# Shutdown_2019_v1_0.net
KiCad netlist of a schematic drawn in EAGLE
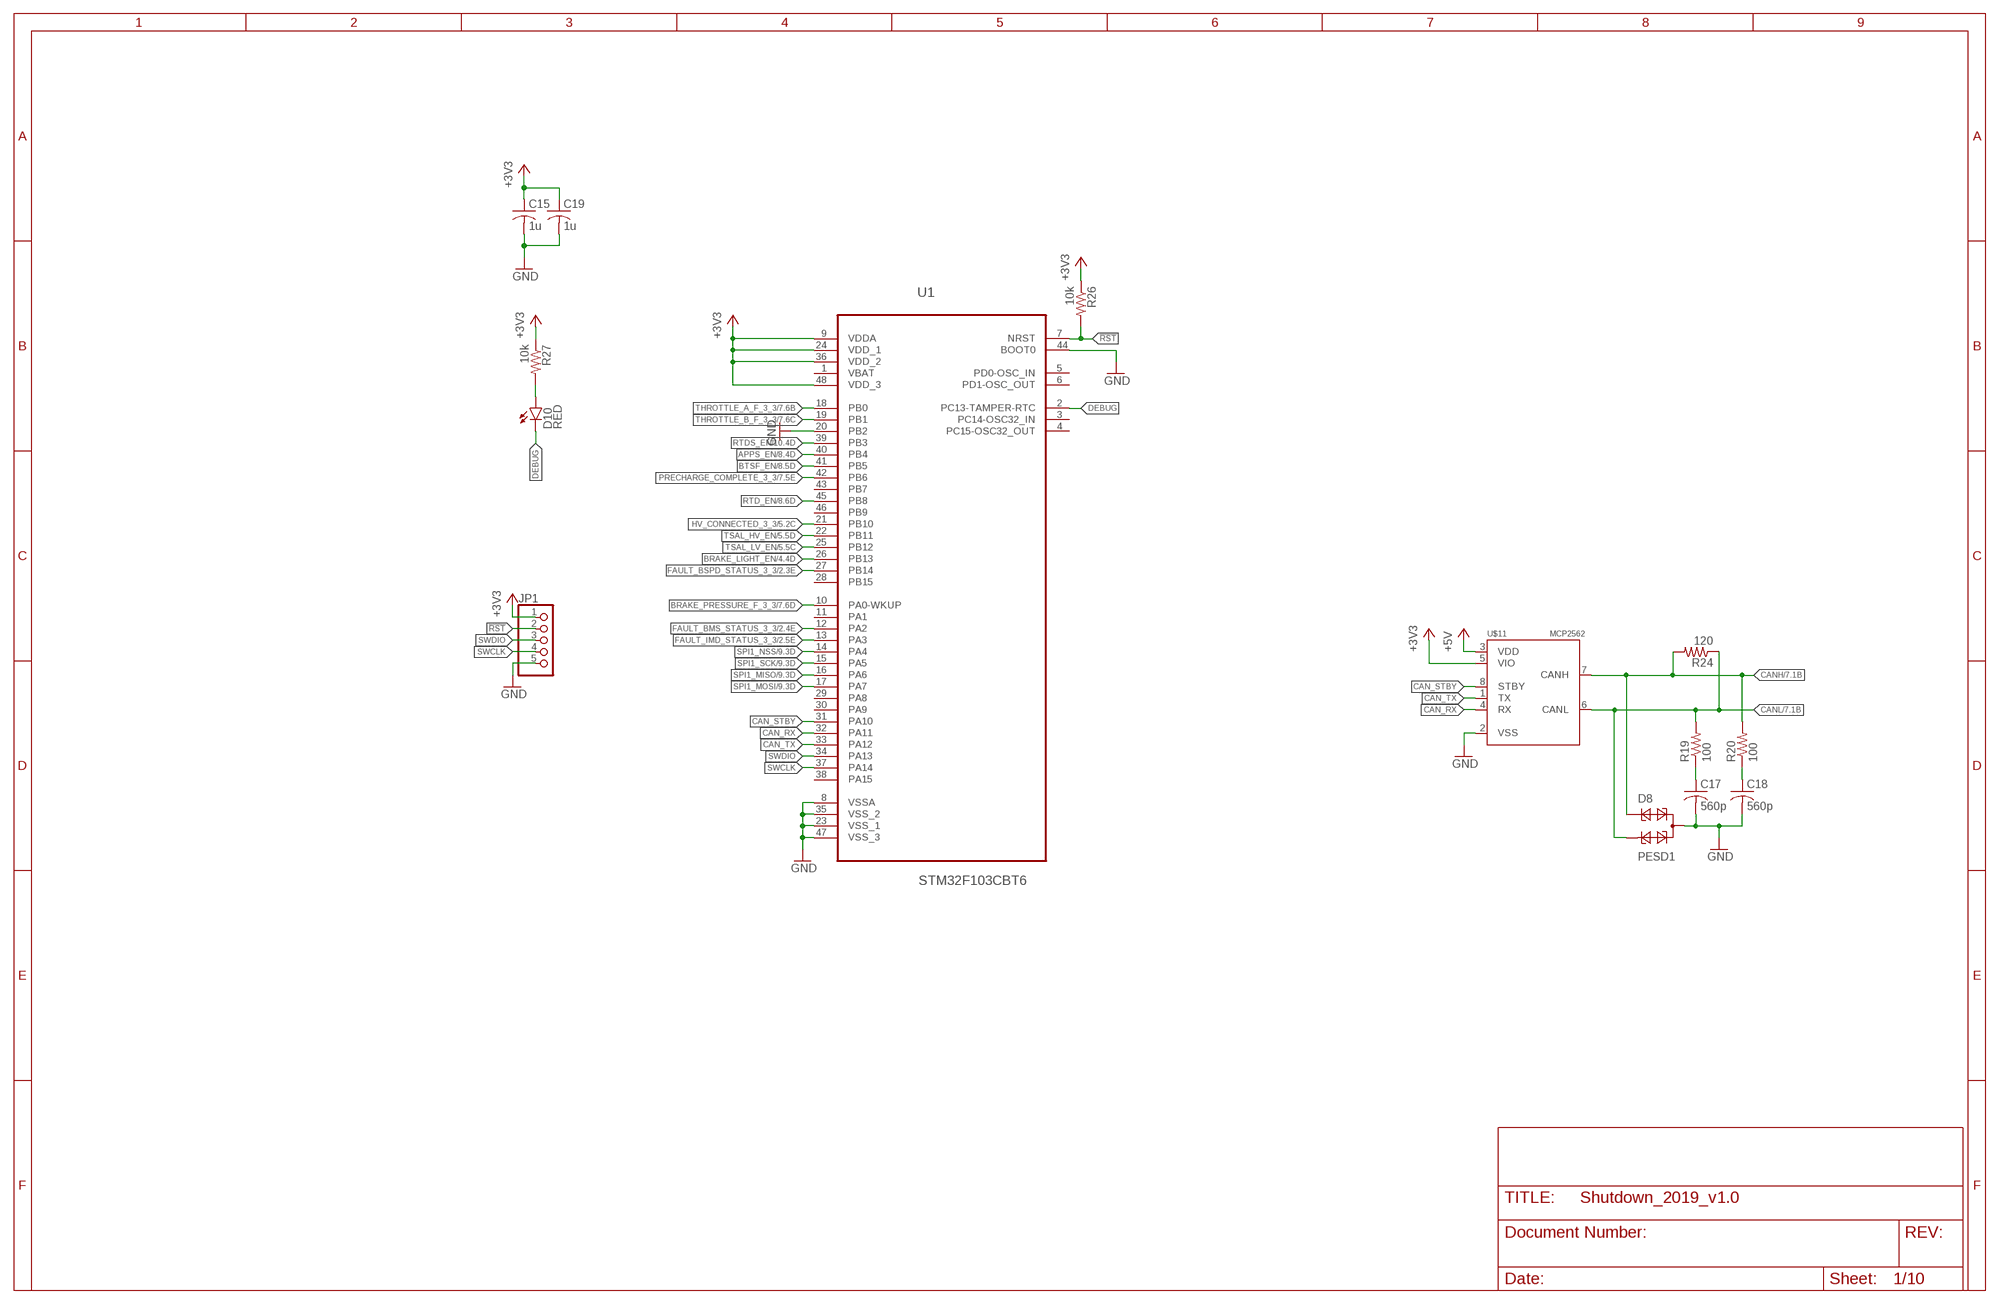
[diagram p0: schematic, sheet 1]
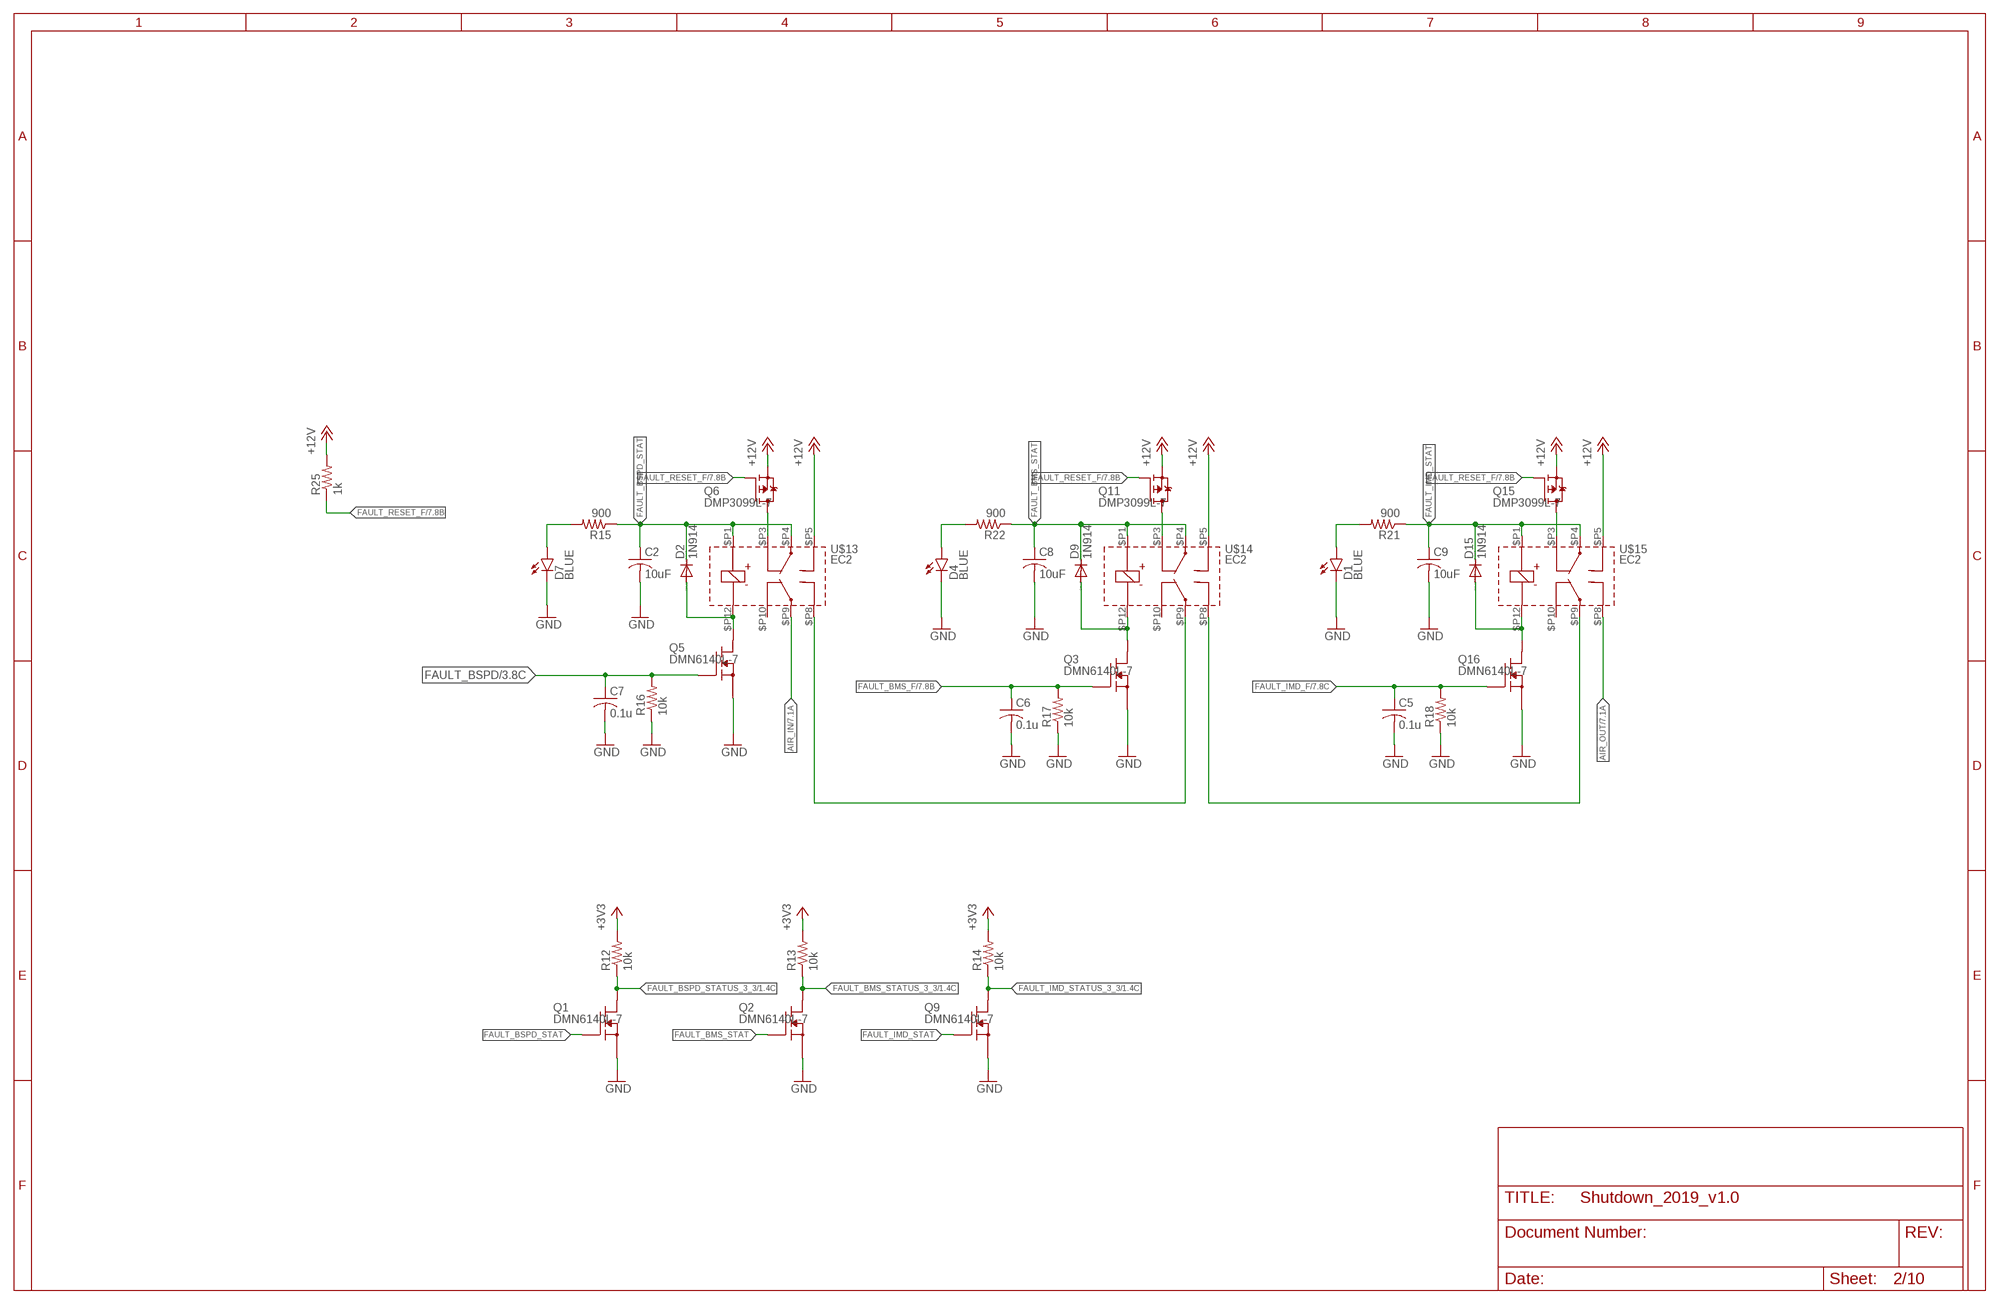
[diagram p1: schematic, sheet 2]
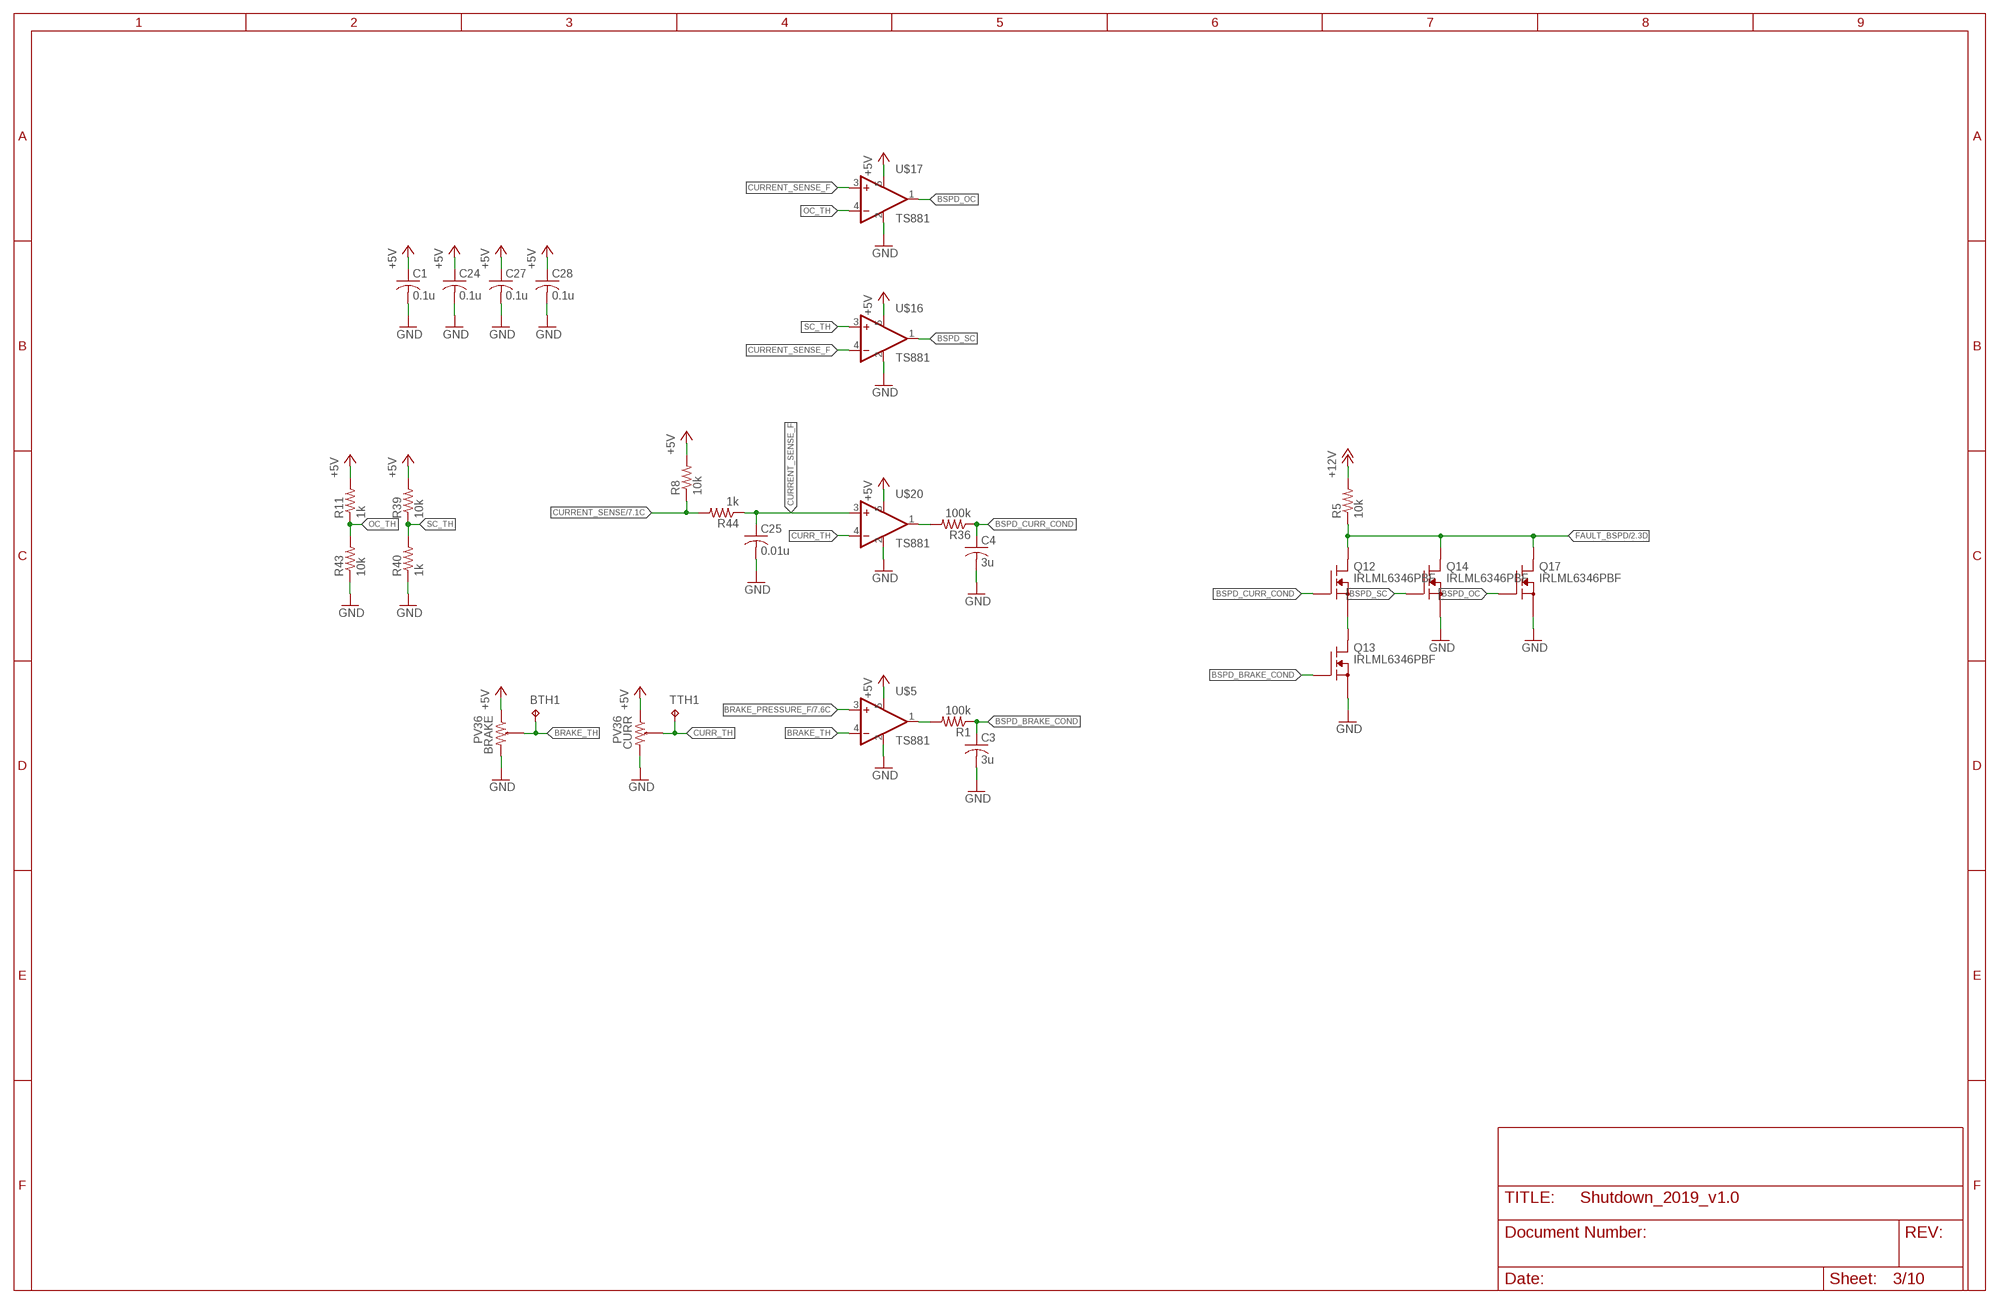
[diagram p2: schematic, sheet 3]
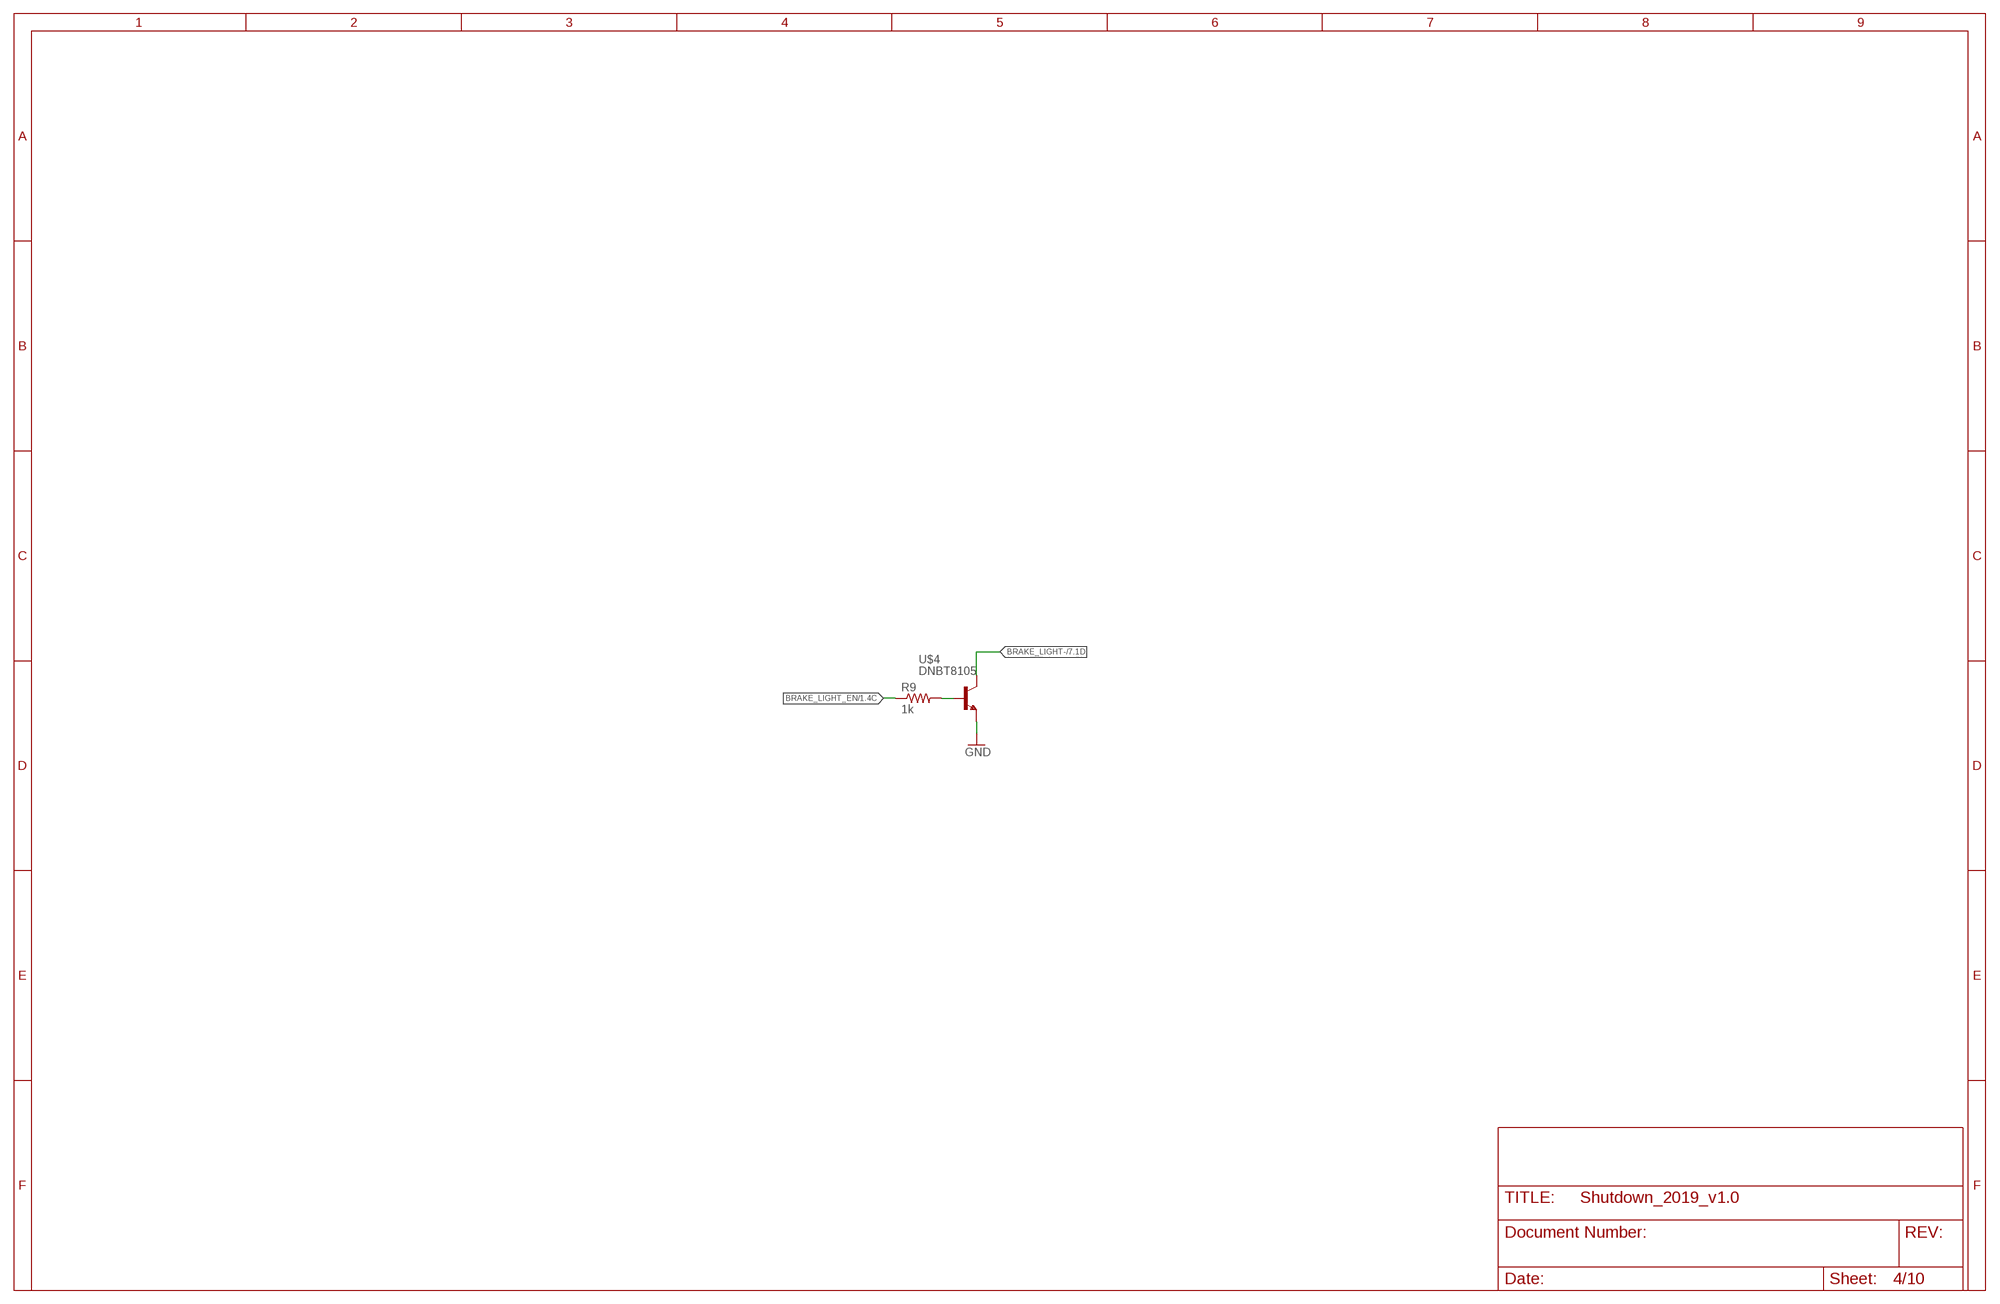
[diagram p3: schematic, sheet 4]
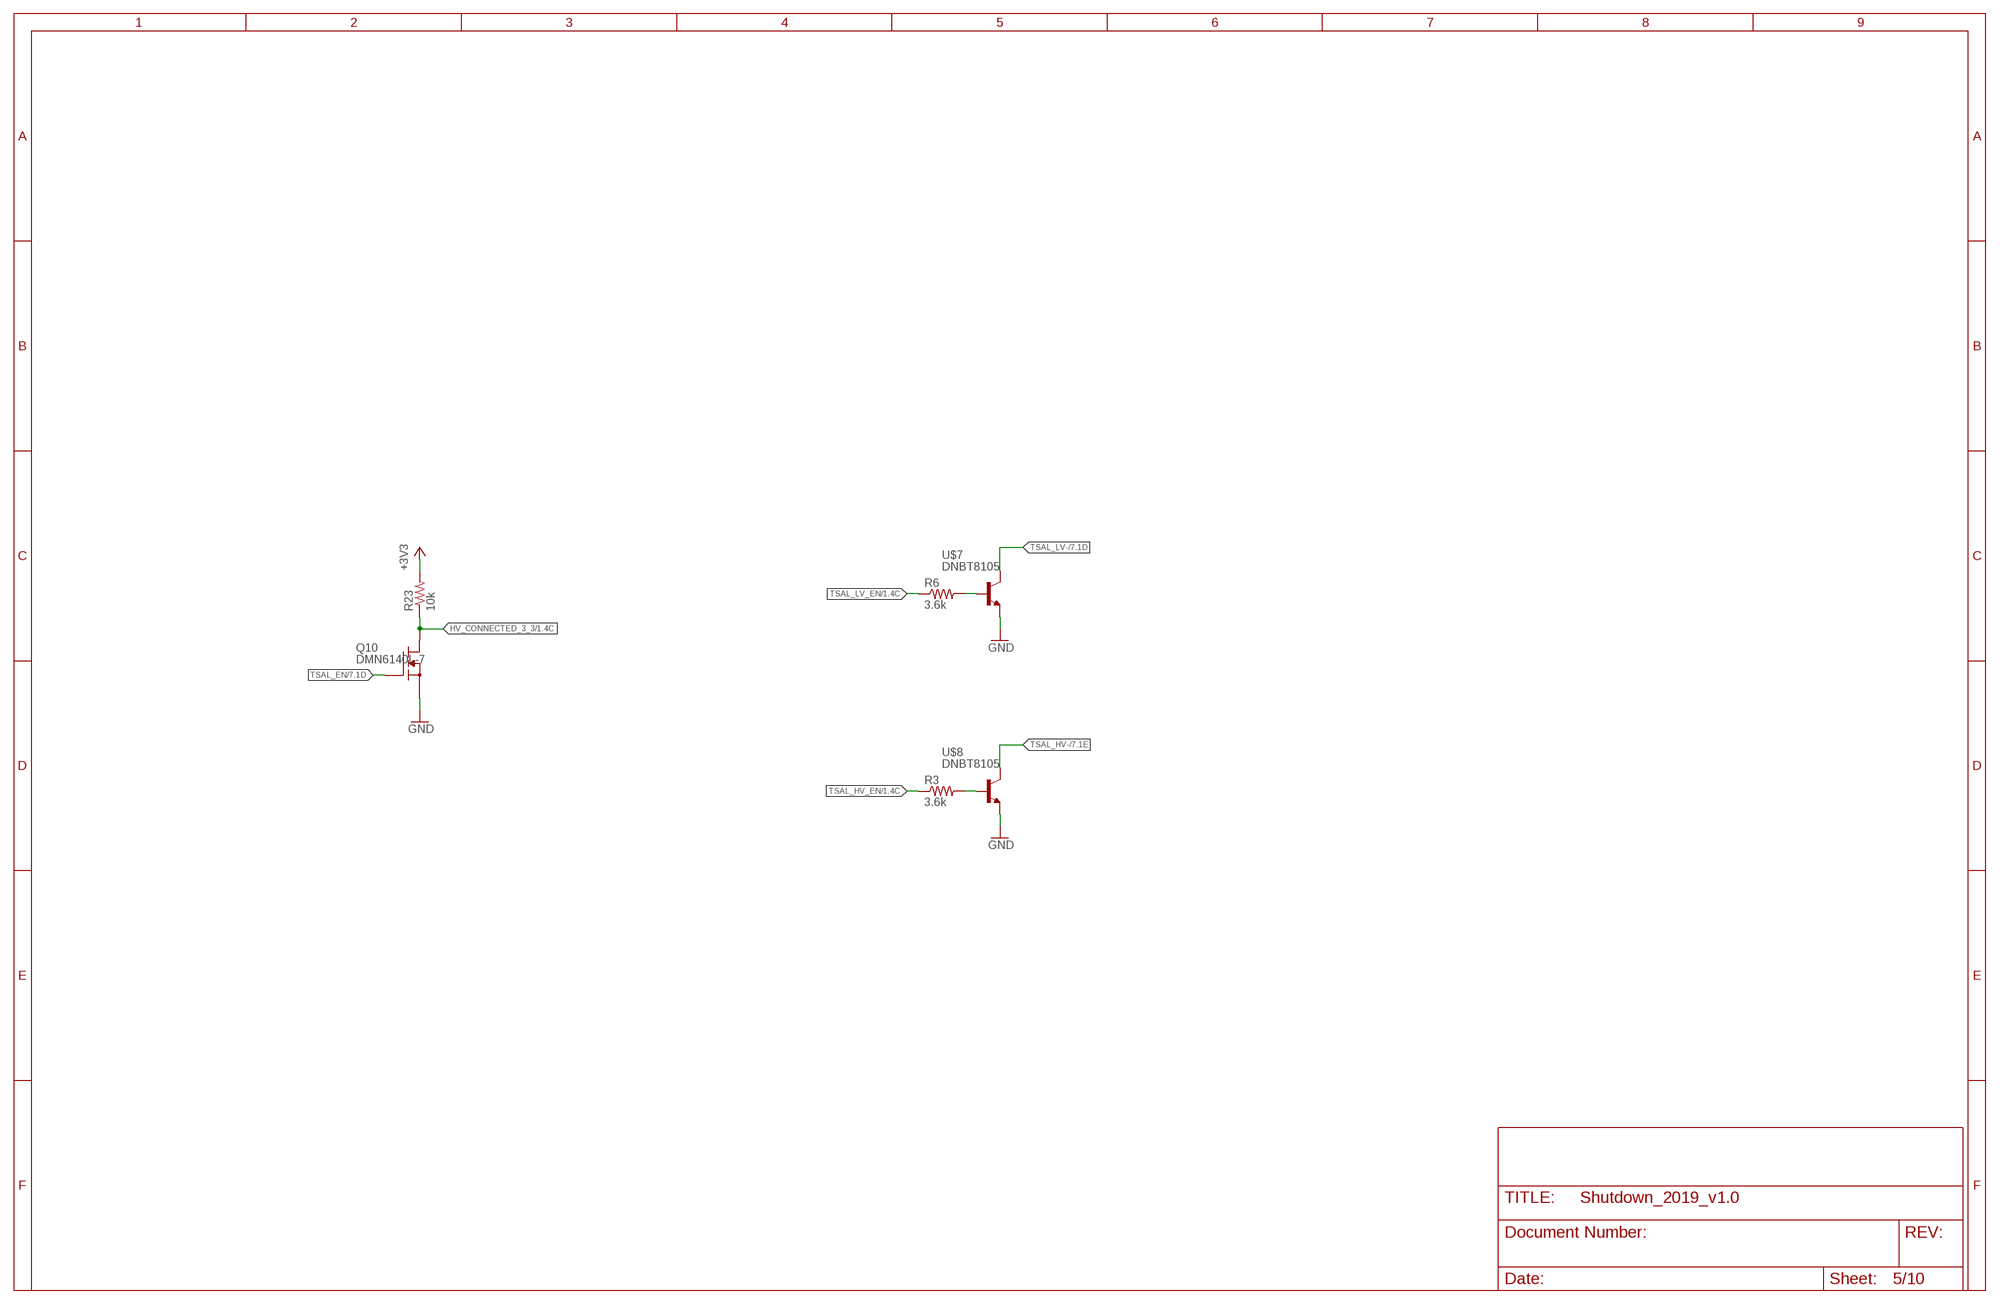
[diagram p4: schematic, sheet 5]
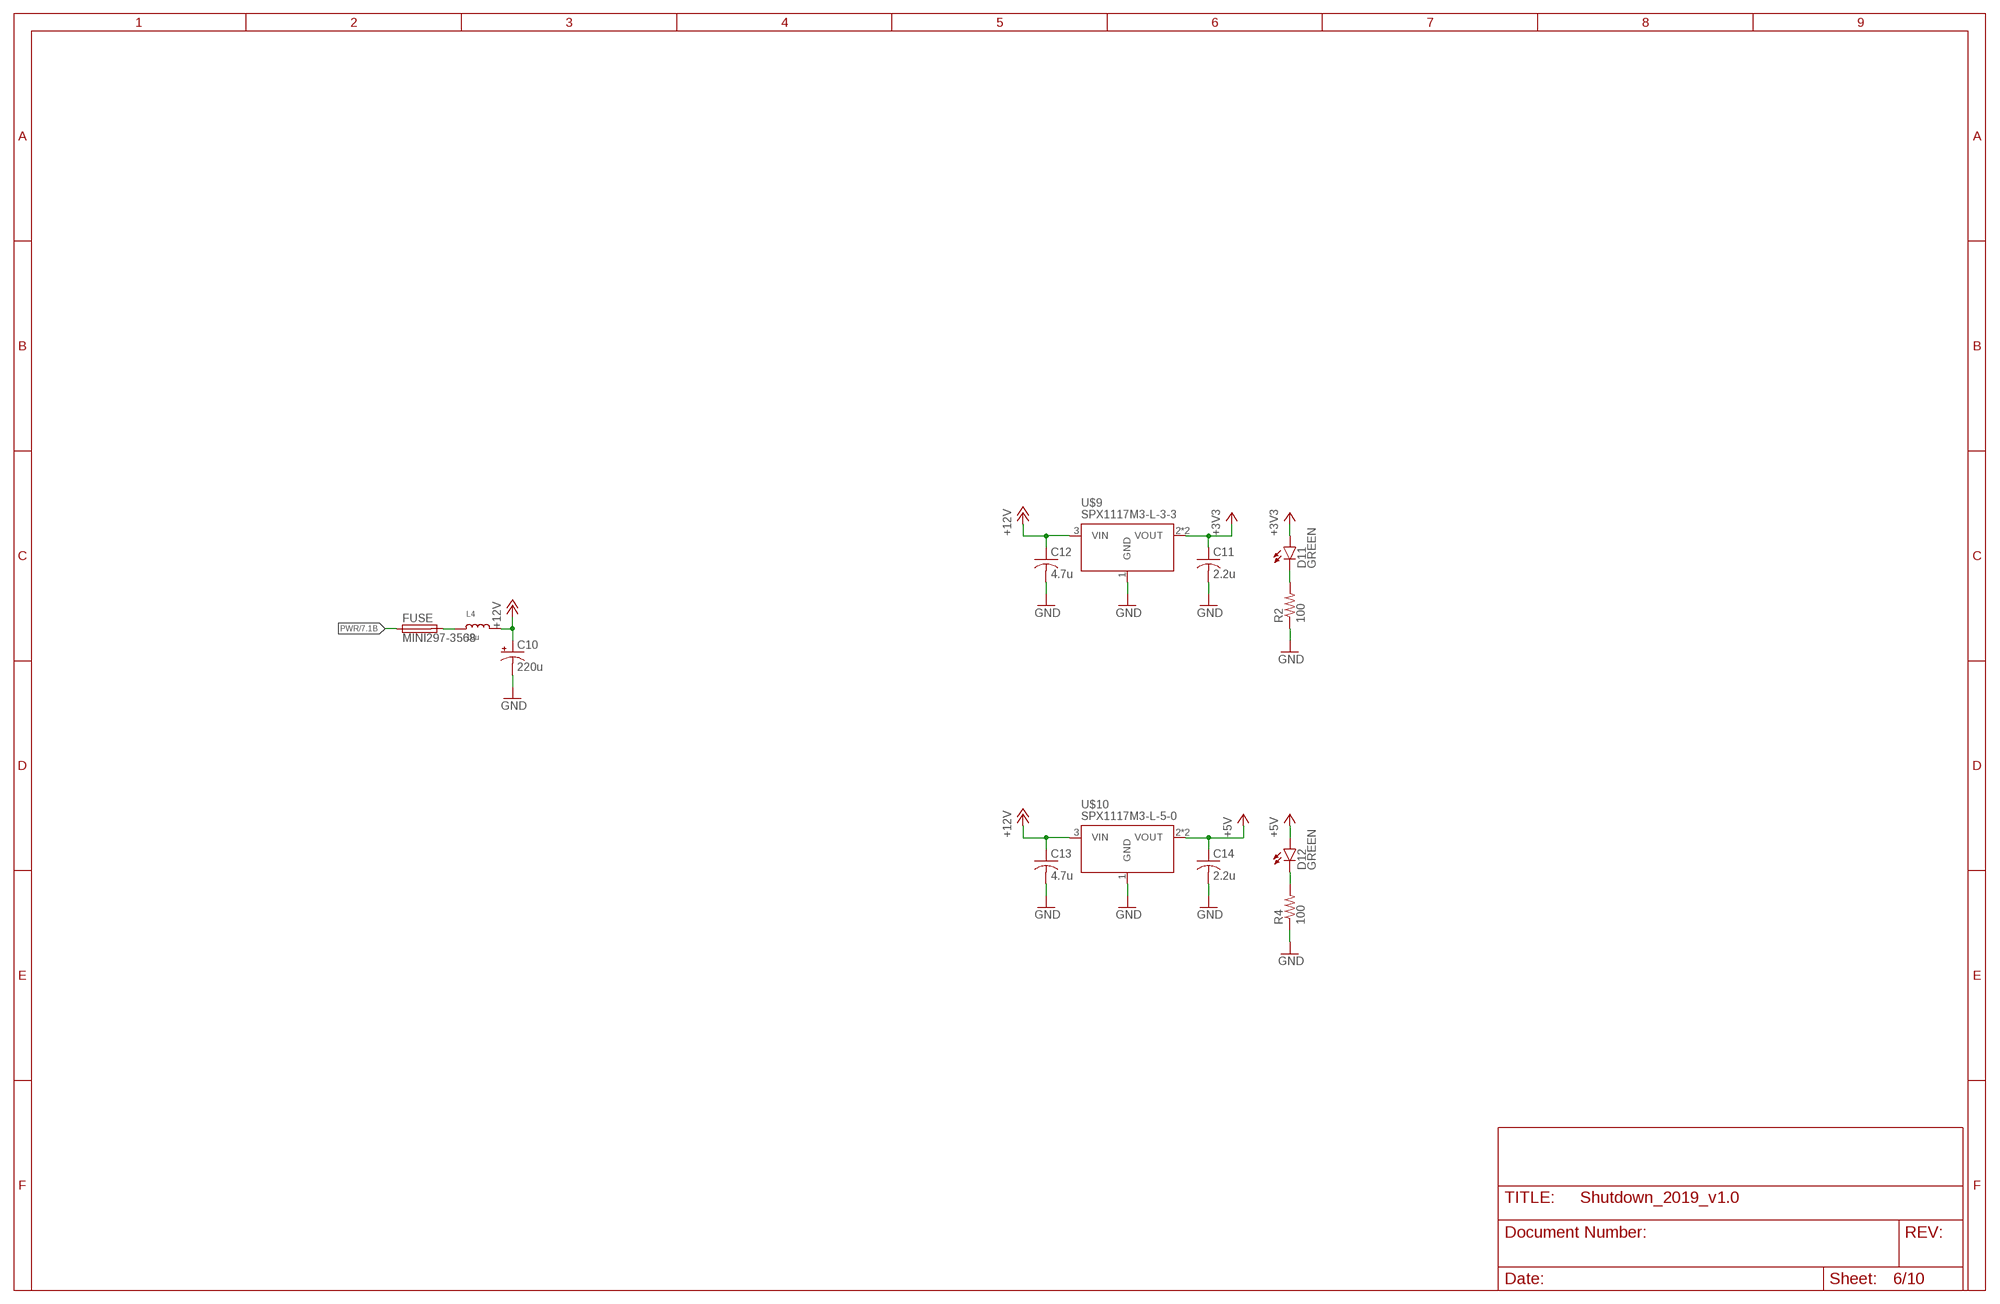
[diagram p5: schematic, sheet 6]
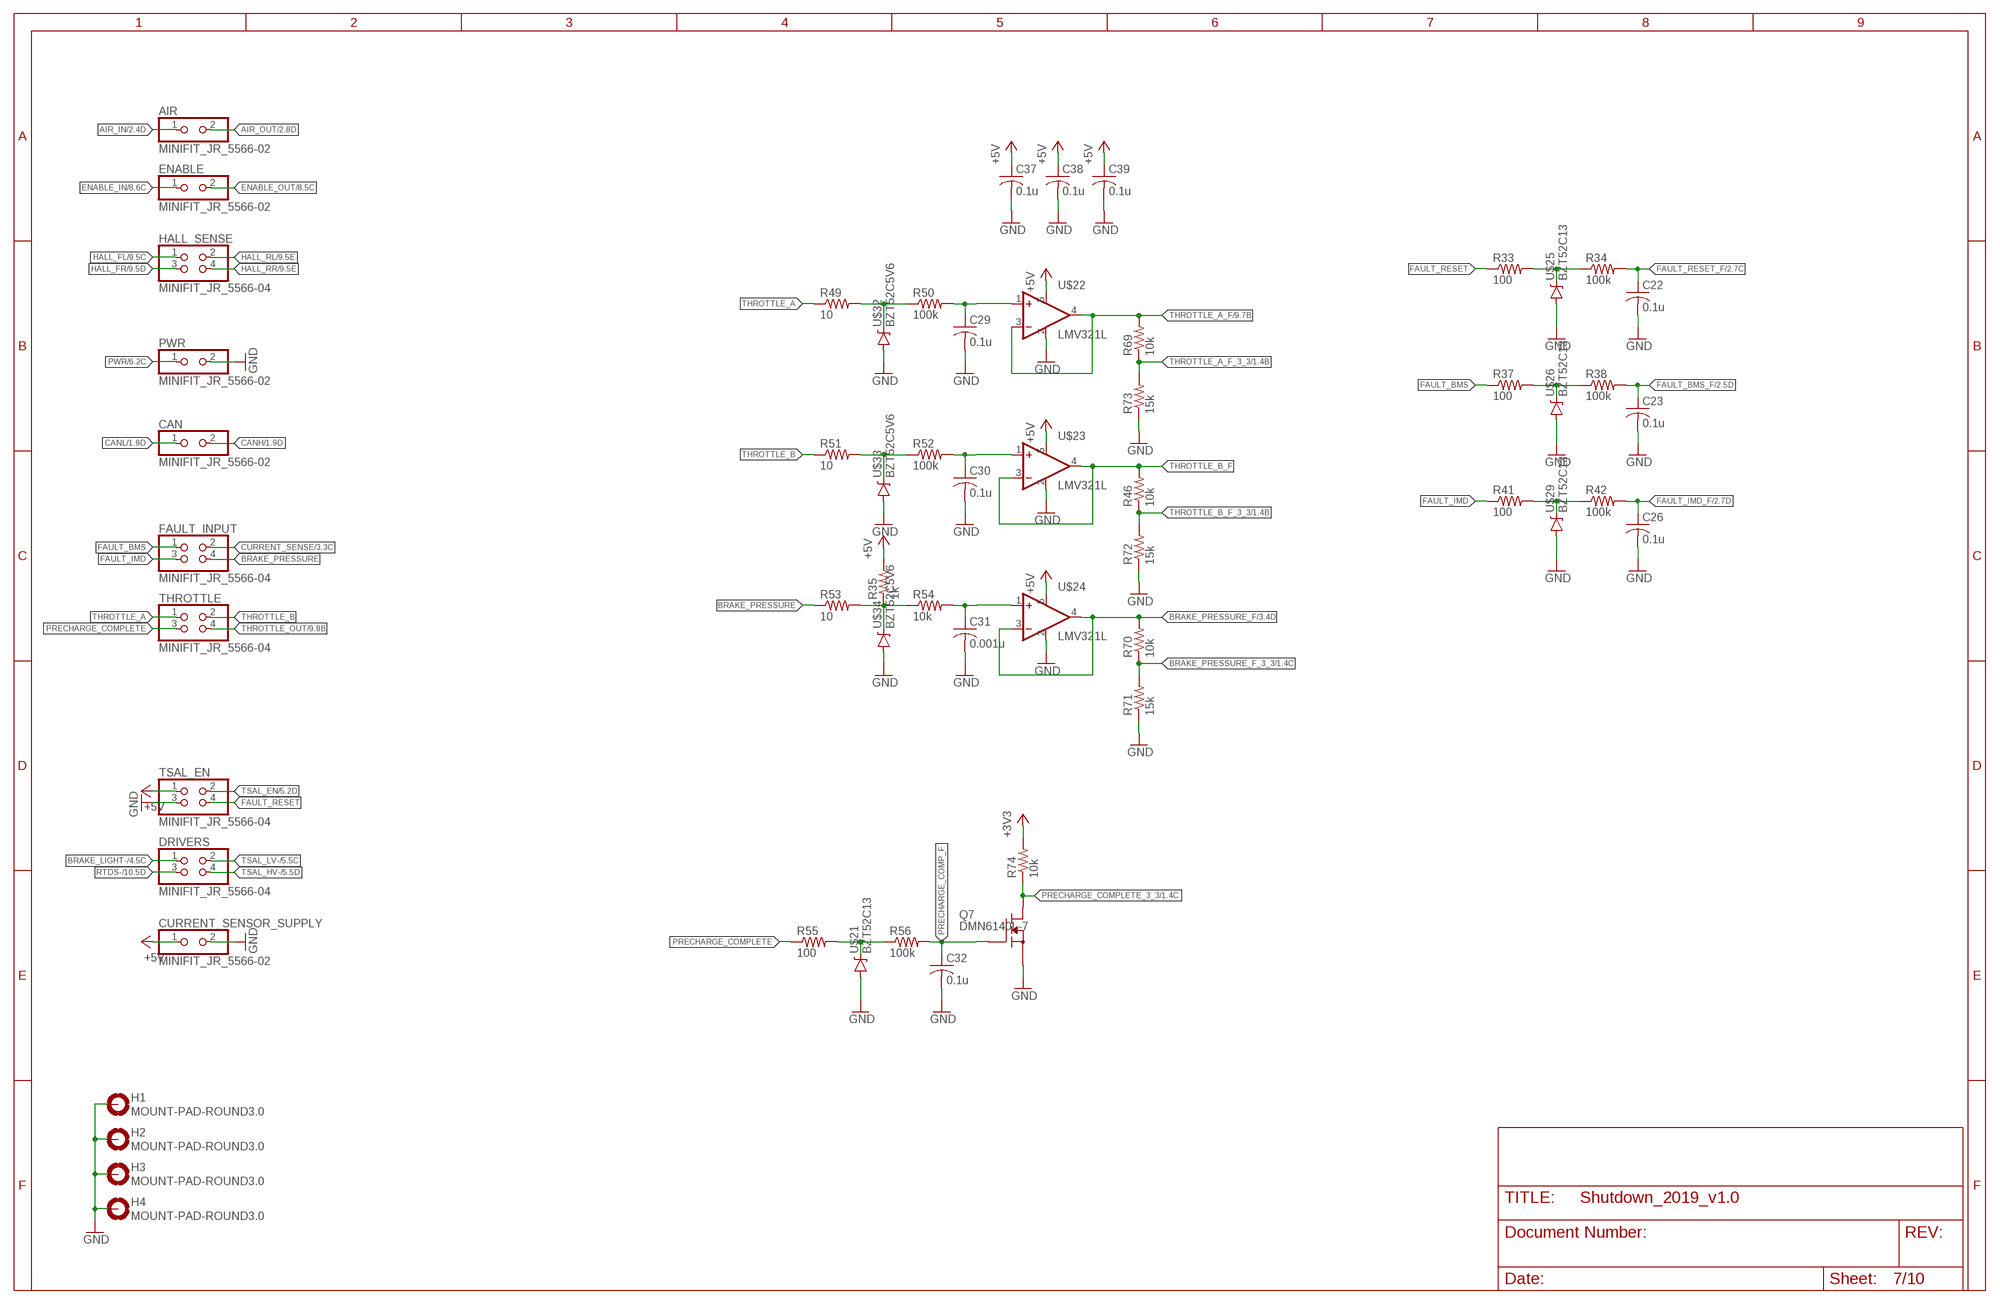
[diagram p6: schematic, sheet 7]
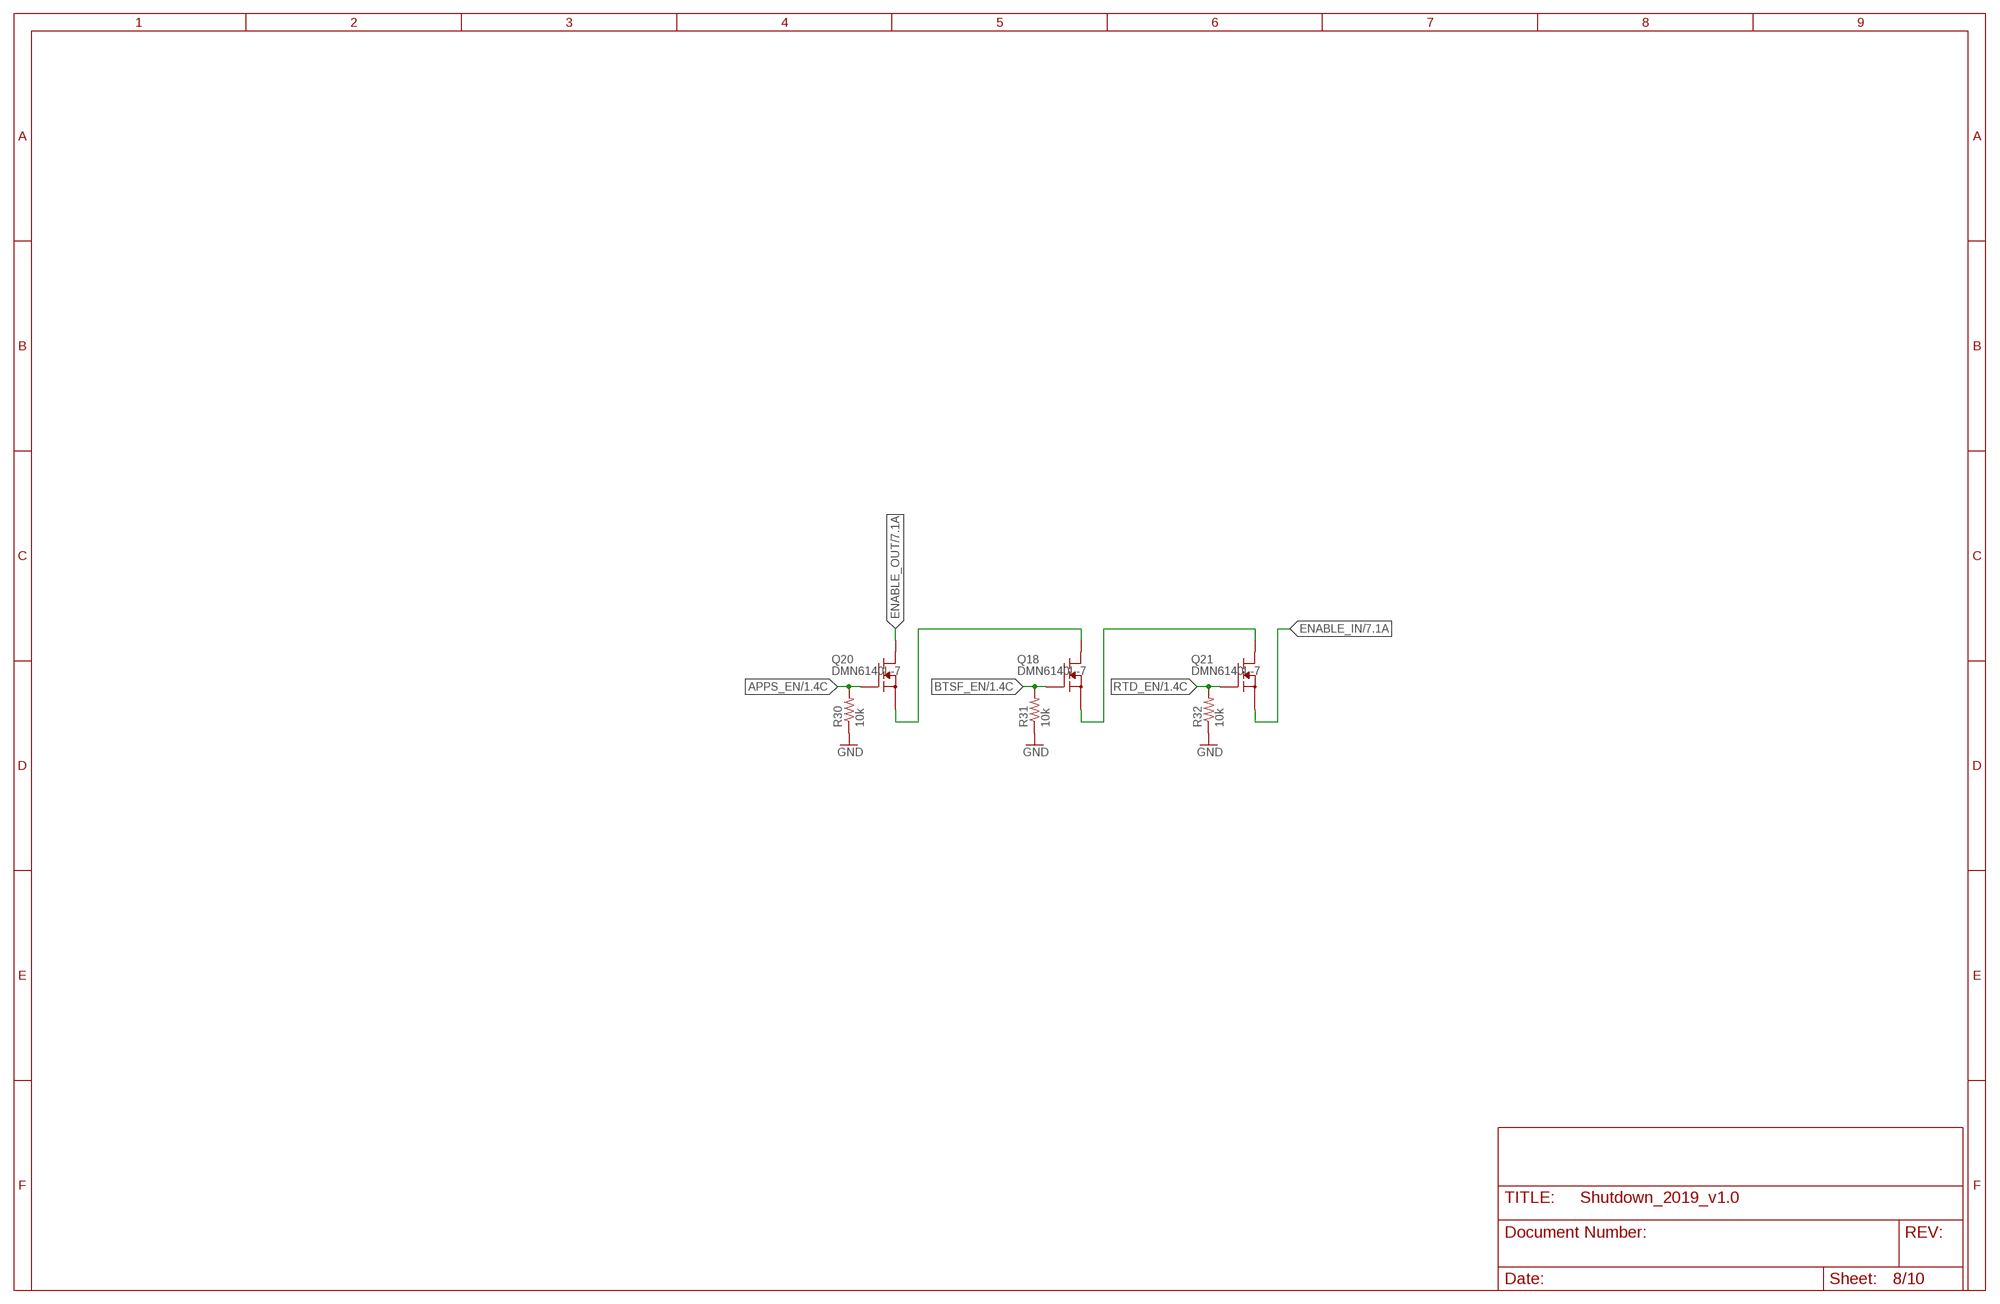
[diagram p7: schematic, sheet 8]
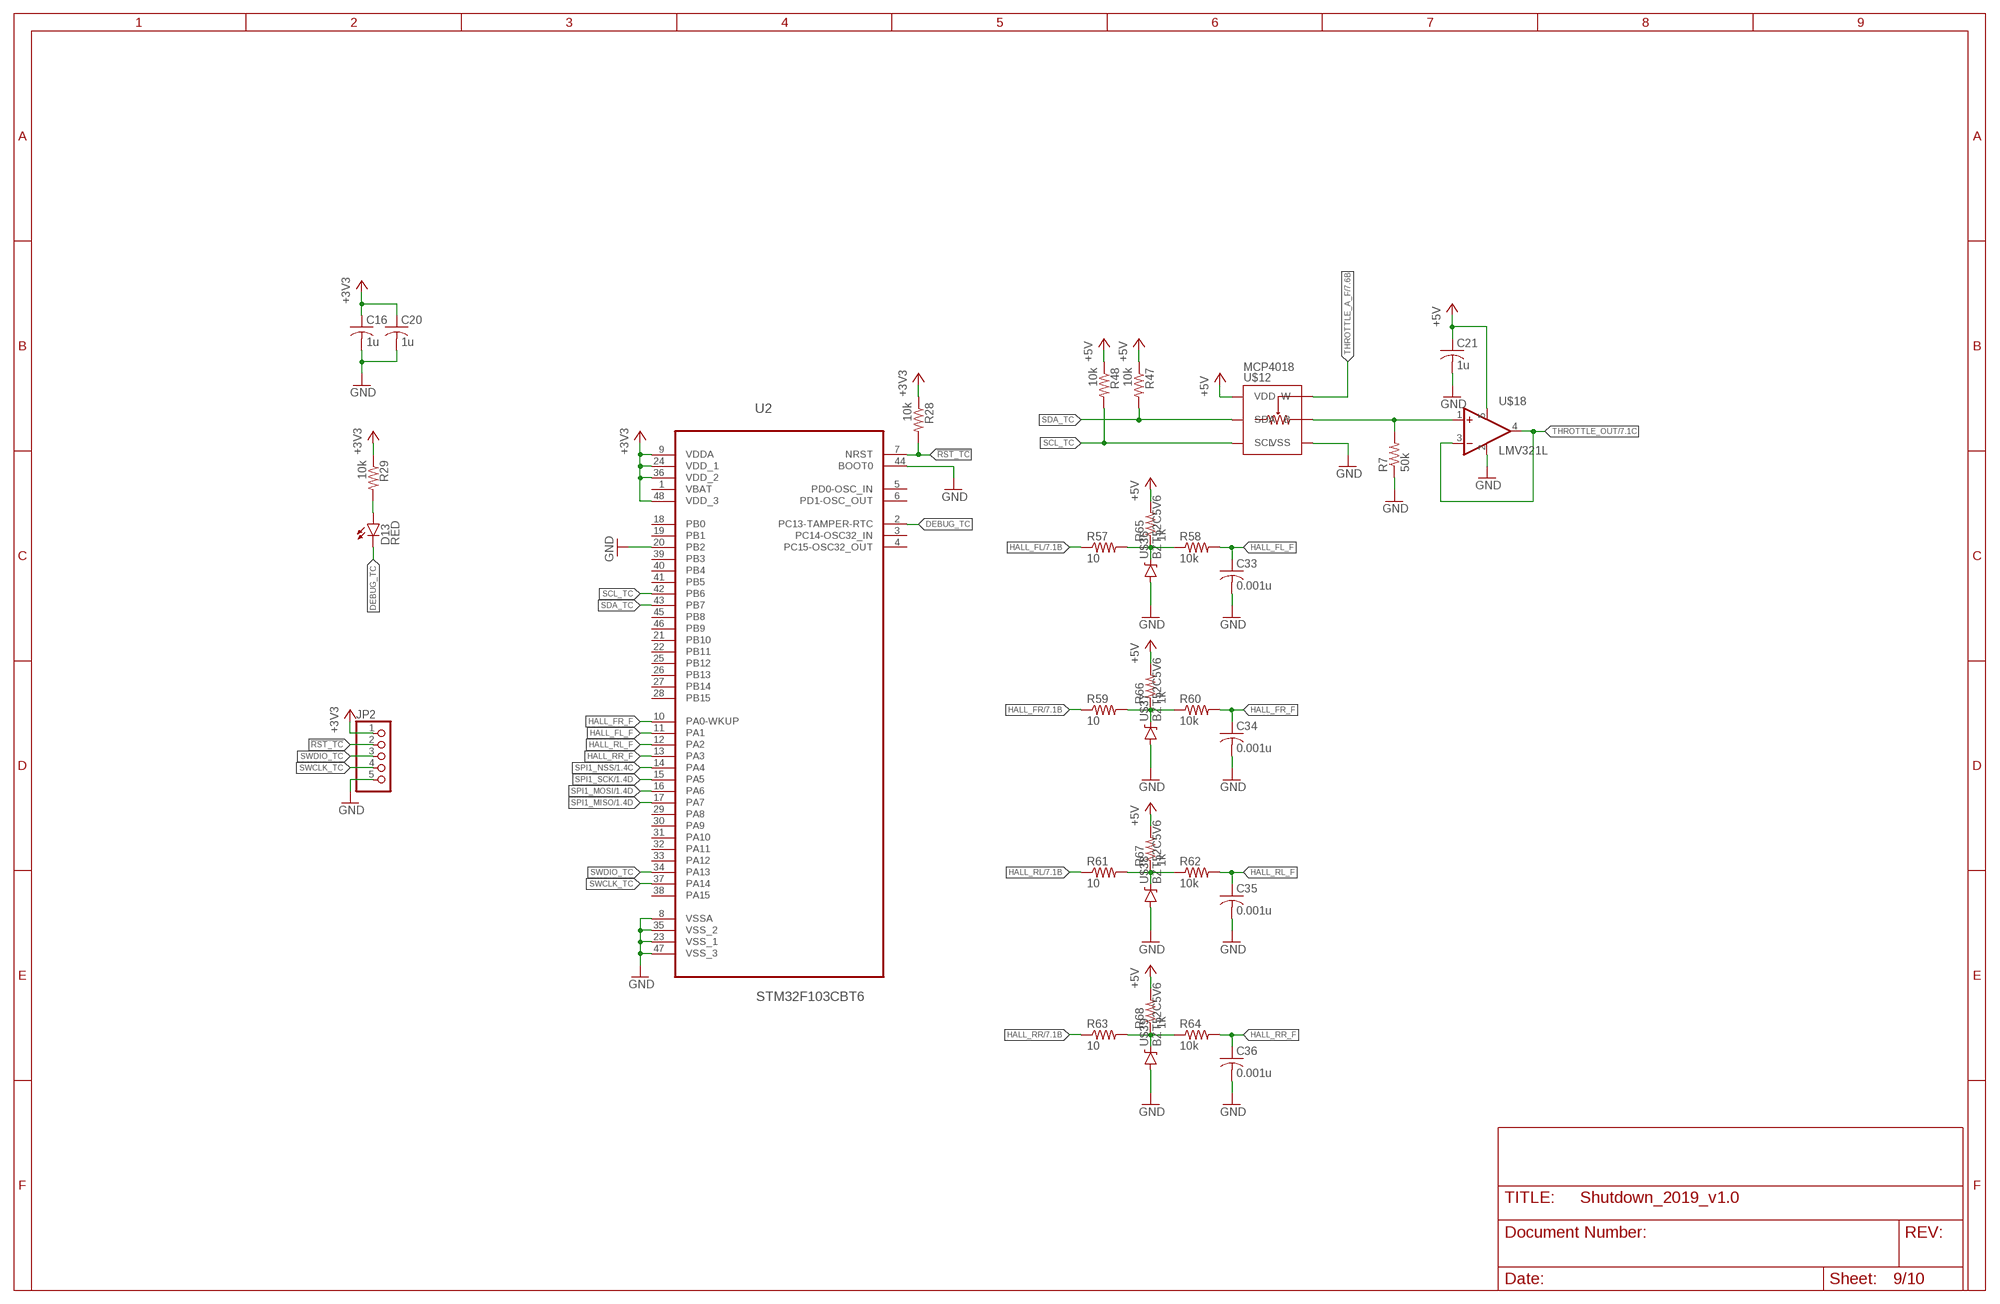
[diagram p8: schematic, sheet 9]
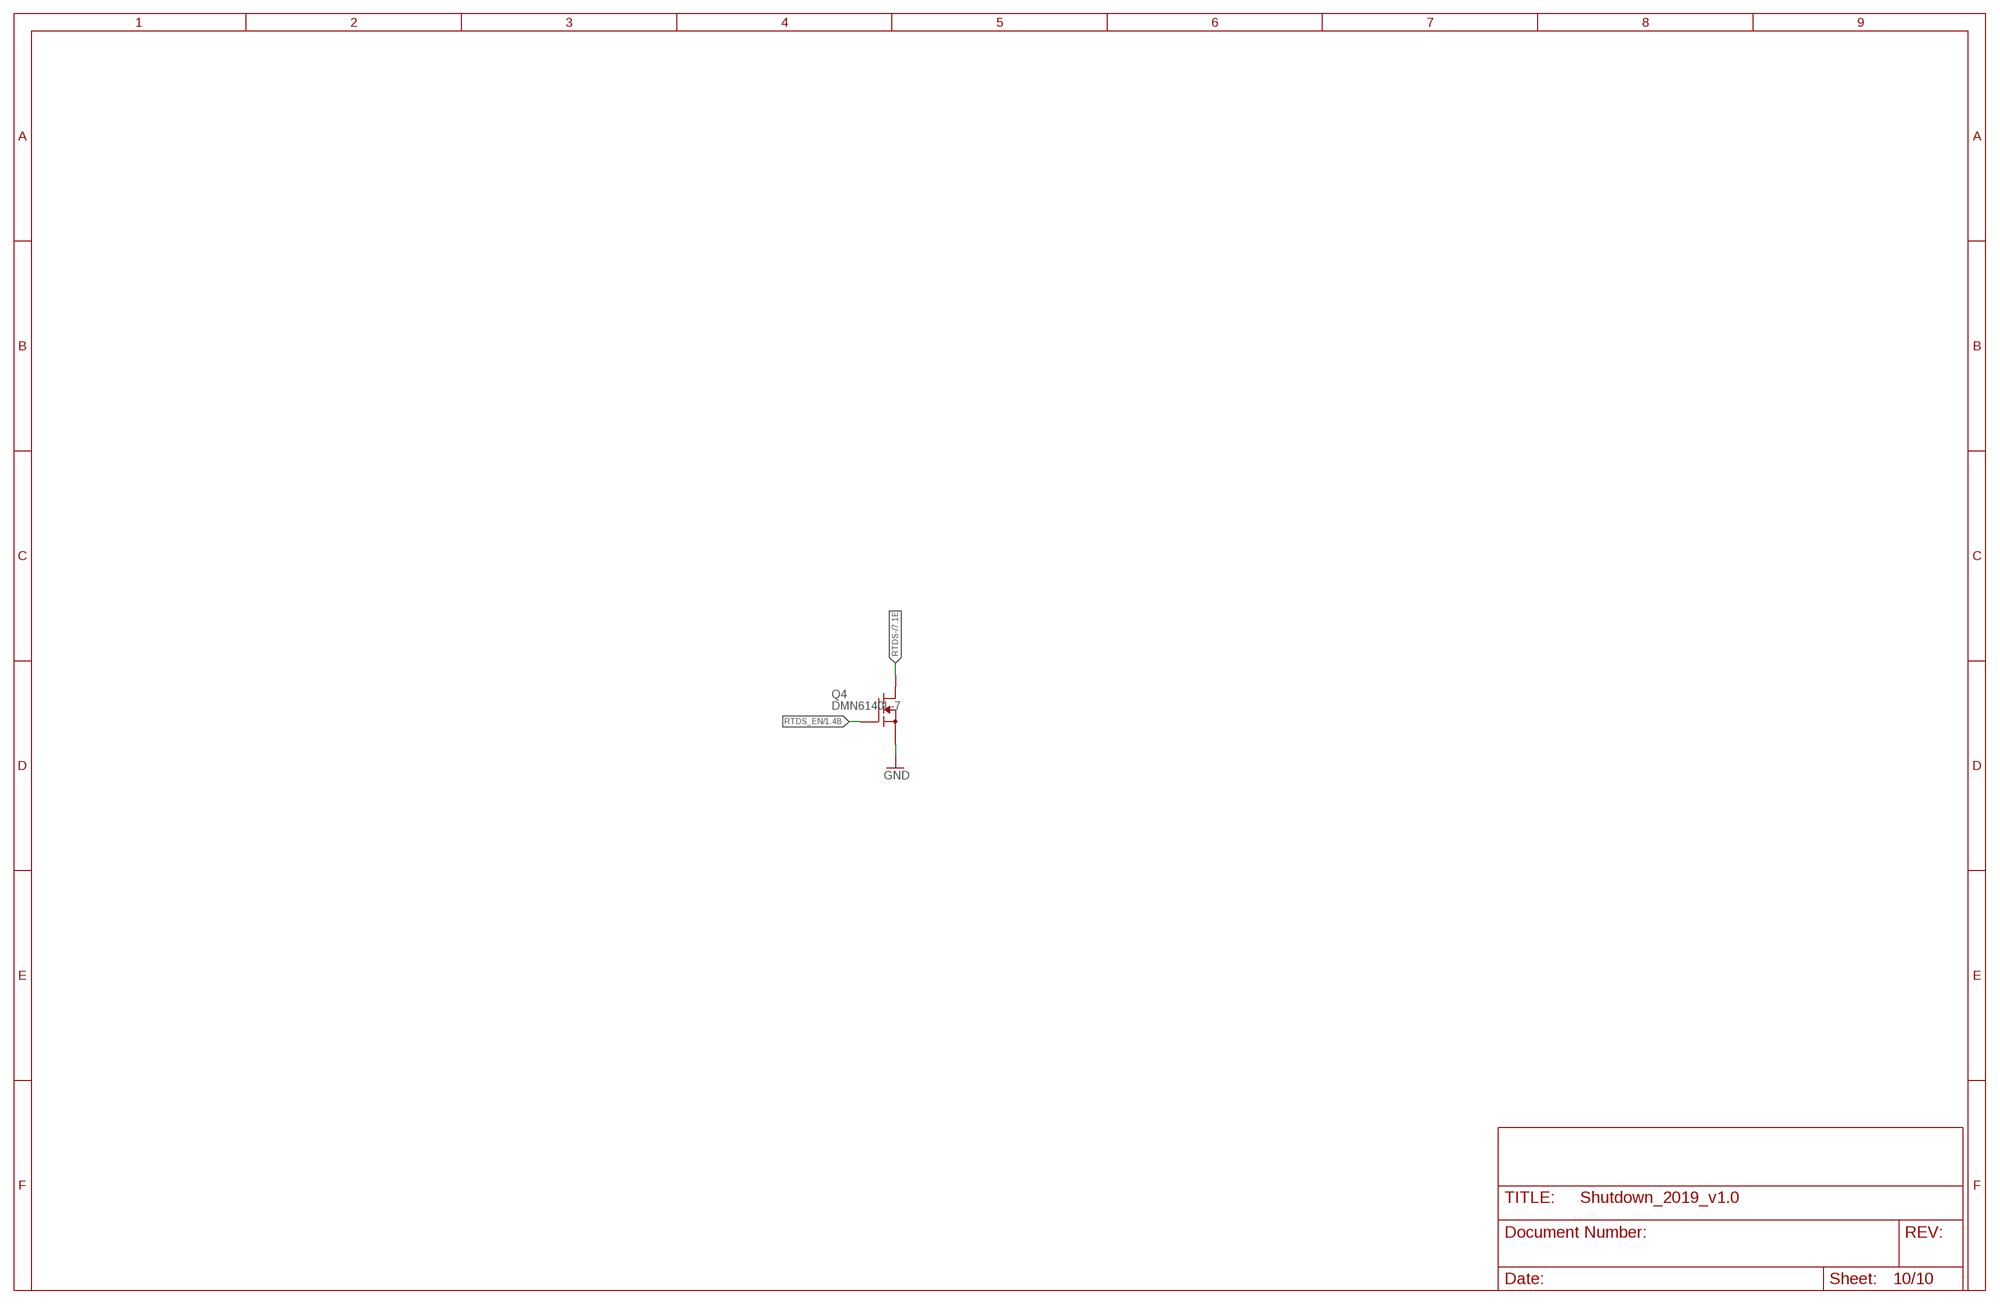
[diagram p9: schematic, sheet 10]

(export (version "E")
  (design (tool "Eeschema 10.0.6"))
  (components
    (comp (ref "C15")
      (value "1u")
      (footprint "eagle-import:C0805")
      (libsource (lib "eagle-import") (part "C-USC0805"))
    )
    (comp (ref "C17")
      (value "560p")
      (footprint "eagle-import:C0603")
      (libsource (lib "eagle-import") (part "C-USC0603"))
    )
    (comp (ref "C18")
      (value "560p")
      (footprint "eagle-import:C0603")
      (libsource (lib "eagle-import") (part "C-USC0603"))
    )
    (comp (ref "C19")
      (value "1u")
      (footprint "eagle-import:C0805")
      (libsource (lib "eagle-import") (part "C-USC0805"))
    )
    (comp (ref "D8")
      (value "PESD1")
      (footprint "eagle-import:SOT23")
      (libsource (lib "eagle-import") (part "PESD1CAN"))
    )
    (comp (ref "D10")
      (value "RED")
      (footprint "eagle-import:LED-0603")
      (libsource (lib "eagle-import") (part "LED-RED0603"))
    )
    (comp (ref "JP1")
      (value "PINHD-1X5")
      (footprint "eagle-import:1X05")
      (libsource (lib "eagle-import") (part "PINHD-1X5"))
    )
    (comp (ref "R19")
      (value "100")
      (footprint "eagle-import:R0603")
      (libsource (lib "eagle-import") (part "R-US_R0603"))
    )
    (comp (ref "R20")
      (value "100")
      (footprint "eagle-import:R0603")
      (libsource (lib "eagle-import") (part "R-US_R0603"))
    )
    (comp (ref "R24")
      (value "120")
      (footprint "eagle-import:R0603")
      (libsource (lib "eagle-import") (part "R-US_R0603"))
    )
    (comp (ref "R26")
      (value "10k")
      (footprint "eagle-import:R0603")
      (libsource (lib "eagle-import") (part "R-US_R0603"))
    )
    (comp (ref "R27")
      (value "10k")
      (footprint "eagle-import:R0603")
      (libsource (lib "eagle-import") (part "R-US_R0603"))
    )
    (comp (ref "U$11")
      (value "MCP2562")
      (footprint "eagle-import:SOIC8")
      (libsource (lib "eagle-import") (part "MCP2562"))
    )
    (comp (ref "U1")
      (value "STM32F103CBT6")
      (footprint "eagle-import:QFP50P900X900X160-48N")
      (libsource (lib "eagle-import") (part "STM32F103CBT6"))
    )
    (comp (ref "C10")
      (value "220u")
      (footprint "eagle-import:E2,5-7")
      (libsource (lib "eagle-import") (part "CPOL-USE2.5-7"))
    )
    (comp (ref "C11")
      (value "2.2u")
      (footprint "eagle-import:C0805")
      (libsource (lib "eagle-import") (part "C-USC0805"))
    )
    (comp (ref "C12")
      (value "4.7u")
      (footprint "eagle-import:C0805")
      (libsource (lib "eagle-import") (part "C-USC0805"))
    )
    (comp (ref "C13")
      (value "4.7u")
      (footprint "eagle-import:C0805")
      (libsource (lib "eagle-import") (part "C-USC0805"))
    )
    (comp (ref "C14")
      (value "2.2u")
      (footprint "eagle-import:C0805")
      (libsource (lib "eagle-import") (part "C-USC0805"))
    )
    (comp (ref "D11")
      (value "GREEN")
      (footprint "eagle-import:LED-0603")
      (libsource (lib "eagle-import") (part "LED-GREEN0603"))
    )
    (comp (ref "D12")
      (value "GREEN")
      (footprint "eagle-import:LED-0603")
      (libsource (lib "eagle-import") (part "LED-GREEN0603"))
    )
    (comp (ref "FUSE")
      (value "MINI297-3568")
      (footprint "eagle-import:3568")
      (libsource (lib "eagle-import") (part "MINI297-3568"))
    )
    (comp (ref "L4")
      (value "10u")
      (footprint "eagle-import:INDUCTOR_5X5MM_NR5040_NOTHERMALS")
      (libsource (lib "eagle-import") (part "INDUCTORNR5040"))
    )
    (comp (ref "R2")
      (value "100")
      (footprint "eagle-import:R0603")
      (libsource (lib "eagle-import") (part "R-US_R0603"))
    )
    (comp (ref "R4")
      (value "100")
      (footprint "eagle-import:R0603")
      (libsource (lib "eagle-import") (part "R-US_R0603"))
    )
    (comp (ref "U$9")
      (value "SPX1117M3-L-3-3")
      (footprint "eagle-import:SOT223")
      (libsource (lib "eagle-import") (part "SPX1117M3-L-3-3"))
    )
    (comp (ref "U$10")
      (value "SPX1117M3-L-5-0")
      (footprint "eagle-import:SOT223")
      (libsource (lib "eagle-import") (part "SPX1117M3-L-5-0"))
    )
    (comp (ref "AIR")
      (value "MINIFIT_JR_5566-02")
      (footprint "eagle-import:MINIFIT_JR_5566-02")
      (libsource (lib "eagle-import") (part "MINIFIT_JR_5566-02"))
    )
    (comp (ref "C22")
      (value "0.1u")
      (footprint "eagle-import:C0805")
      (libsource (lib "eagle-import") (part "C-USC0805"))
    )
    (comp (ref "C23")
      (value "0.1u")
      (footprint "eagle-import:C0805")
      (libsource (lib "eagle-import") (part "C-USC0805"))
    )
    (comp (ref "C26")
      (value "0.1u")
      (footprint "eagle-import:C0805")
      (libsource (lib "eagle-import") (part "C-USC0805"))
    )
    (comp (ref "C29")
      (value "0.1u")
      (footprint "eagle-import:C0805")
      (libsource (lib "eagle-import") (part "C-USC0805"))
    )
    (comp (ref "C30")
      (value "0.1u")
      (footprint "eagle-import:C0805")
      (libsource (lib "eagle-import") (part "C-USC0805"))
    )
    (comp (ref "C31")
      (value "0.001u")
      (footprint "eagle-import:C0805")
      (libsource (lib "eagle-import") (part "C-USC0805"))
    )
    (comp (ref "C32")
      (value "0.1u")
      (footprint "eagle-import:C0805")
      (libsource (lib "eagle-import") (part "C-USC0805"))
    )
    (comp (ref "C37")
      (value "0.1u")
      (footprint "eagle-import:C0603")
      (libsource (lib "eagle-import") (part "resistor_348_C-USC0603"))
    )
    (comp (ref "C38")
      (value "0.1u")
      (footprint "eagle-import:C0603")
      (libsource (lib "eagle-import") (part "resistor_348_C-USC0603"))
    )
    (comp (ref "C39")
      (value "0.1u")
      (footprint "eagle-import:C0603")
      (libsource (lib "eagle-import") (part "resistor_348_C-USC0603"))
    )
    (comp (ref "CAN")
      (value "MINIFIT_JR_5566-02")
      (footprint "eagle-import:MINIFIT_JR_5566-02")
      (libsource (lib "eagle-import") (part "MINIFIT_JR_5566-02"))
    )
    (comp (ref "CURRENT_SENSOR_SUPPLY")
      (value "MINIFIT_JR_5566-02")
      (footprint "eagle-import:MINIFIT_JR_5566-02")
      (libsource (lib "eagle-import") (part "MINIFIT_JR_5566-02"))
    )
    (comp (ref "DRIVERS")
      (value "MINIFIT_JR_5566-04")
      (footprint "eagle-import:MINIFIT_JR_5566-04")
      (libsource (lib "eagle-import") (part "MINIFIT_JR_5566-04"))
    )
    (comp (ref "ENABLE")
      (value "MINIFIT_JR_5566-02")
      (footprint "eagle-import:MINIFIT_JR_5566-02")
      (libsource (lib "eagle-import") (part "MINIFIT_JR_5566-02"))
    )
    (comp (ref "FAULT_INPUT")
      (value "MINIFIT_JR_5566-04")
      (footprint "eagle-import:MINIFIT_JR_5566-04")
      (libsource (lib "eagle-import") (part "MINIFIT_JR_5566-04"))
    )
    (comp (ref "H1")
      (value "MOUNT-PAD-ROUND3.0")
      (footprint "eagle-import:3,0-PAD")
      (libsource (lib "eagle-import") (part "MOUNT-PAD-ROUND3.0"))
    )
    (comp (ref "H2")
      (value "MOUNT-PAD-ROUND3.0")
      (footprint "eagle-import:3,0-PAD")
      (libsource (lib "eagle-import") (part "MOUNT-PAD-ROUND3.0"))
    )
    (comp (ref "H3")
      (value "MOUNT-PAD-ROUND3.0")
      (footprint "eagle-import:3,0-PAD")
      (libsource (lib "eagle-import") (part "MOUNT-PAD-ROUND3.0"))
    )
    (comp (ref "H4")
      (value "MOUNT-PAD-ROUND3.0")
      (footprint "eagle-import:3,0-PAD")
      (libsource (lib "eagle-import") (part "MOUNT-PAD-ROUND3.0"))
    )
    (comp (ref "HALL_SENSE")
      (value "MINIFIT_JR_5566-04")
      (footprint "eagle-import:MINIFIT_JR_5566-04")
      (libsource (lib "eagle-import") (part "MINIFIT_JR_5566-04"))
    )
    (comp (ref "PWR")
      (value "MINIFIT_JR_5566-02")
      (footprint "eagle-import:MINIFIT_JR_5566-02")
      (libsource (lib "eagle-import") (part "MINIFIT_JR_5566-02"))
    )
    (comp (ref "Q7")
      (value "DMN6140L-7")
      (footprint "eagle-import:SOT23")
      (libsource (lib "eagle-import") (part "DMN6140L-7"))
    )
    (comp (ref "R33")
      (value "100")
      (footprint "eagle-import:R0603")
      (libsource (lib "eagle-import") (part "R-US_R0603"))
    )
    (comp (ref "R34")
      (value "100k")
      (footprint "eagle-import:R0603")
      (libsource (lib "eagle-import") (part "R-US_R0603"))
    )
    (comp (ref "R35")
      (value "1k")
      (footprint "eagle-import:R0603")
      (libsource (lib "eagle-import") (part "R-US_R0603"))
    )
    (comp (ref "R37")
      (value "100")
      (footprint "eagle-import:R0603")
      (libsource (lib "eagle-import") (part "R-US_R0603"))
    )
    (comp (ref "R38")
      (value "100k")
      (footprint "eagle-import:R0603")
      (libsource (lib "eagle-import") (part "R-US_R0603"))
    )
    (comp (ref "R41")
      (value "100")
      (footprint "eagle-import:R0603")
      (libsource (lib "eagle-import") (part "R-US_R0603"))
    )
    (comp (ref "R42")
      (value "100k")
      (footprint "eagle-import:R0603")
      (libsource (lib "eagle-import") (part "R-US_R0603"))
    )
    (comp (ref "R46")
      (value "10k")
      (footprint "eagle-import:R0603")
      (libsource (lib "eagle-import") (part "R-US_R0603"))
    )
    (comp (ref "R49")
      (value "10")
      (footprint "eagle-import:R0603")
      (libsource (lib "eagle-import") (part "R-US_R0603"))
    )
    (comp (ref "R50")
      (value "100k")
      (footprint "eagle-import:R0603")
      (libsource (lib "eagle-import") (part "R-US_R0603"))
    )
    (comp (ref "R51")
      (value "10")
      (footprint "eagle-import:R0603")
      (libsource (lib "eagle-import") (part "R-US_R0603"))
    )
    (comp (ref "R52")
      (value "100k")
      (footprint "eagle-import:R0603")
      (libsource (lib "eagle-import") (part "R-US_R0603"))
    )
    (comp (ref "R53")
      (value "10")
      (footprint "eagle-import:R0603")
      (libsource (lib "eagle-import") (part "R-US_R0603"))
    )
    (comp (ref "R54")
      (value "10k")
      (footprint "eagle-import:R0603")
      (libsource (lib "eagle-import") (part "R-US_R0603"))
    )
    (comp (ref "R55")
      (value "100")
      (footprint "eagle-import:R0603")
      (libsource (lib "eagle-import") (part "R-US_R0603"))
    )
    (comp (ref "R56")
      (value "100k")
      (footprint "eagle-import:R0603")
      (libsource (lib "eagle-import") (part "R-US_R0603"))
    )
    (comp (ref "R69")
      (value "10k")
      (footprint "eagle-import:R0603")
      (libsource (lib "eagle-import") (part "R-US_R0603"))
    )
    (comp (ref "R70")
      (value "10k")
      (footprint "eagle-import:R0603")
      (libsource (lib "eagle-import") (part "R-US_R0603"))
    )
    (comp (ref "R71")
      (value "15k")
      (footprint "eagle-import:R0603")
      (libsource (lib "eagle-import") (part "R-US_R0603"))
    )
    (comp (ref "R72")
      (value "15k")
      (footprint "eagle-import:R0603")
      (libsource (lib "eagle-import") (part "R-US_R0603"))
    )
    (comp (ref "R73")
      (value "15k")
      (footprint "eagle-import:R0603")
      (libsource (lib "eagle-import") (part "R-US_R0603"))
    )
    (comp (ref "R74")
      (value "10k")
      (footprint "eagle-import:R0603")
      (libsource (lib "eagle-import") (part "R-US_R0603"))
    )
    (comp (ref "THROTTLE")
      (value "MINIFIT_JR_5566-04")
      (footprint "eagle-import:MINIFIT_JR_5566-04")
      (libsource (lib "eagle-import") (part "MINIFIT_JR_5566-04"))
    )
    (comp (ref "TSAL_EN")
      (value "MINIFIT_JR_5566-04")
      (footprint "eagle-import:MINIFIT_JR_5566-04")
      (libsource (lib "eagle-import") (part "MINIFIT_JR_5566-04"))
    )
    (comp (ref "U$21")
      (value "BZT52C13")
      (footprint "eagle-import:SOD-123")
      (libsource (lib "eagle-import") (part "BZT52C"))
    )
    (comp (ref "U$22")
      (value "LMV321L")
      (footprint "eagle-import:SOT23-5")
      (libsource (lib "eagle-import") (part "LMV321L"))
    )
    (comp (ref "U$23")
      (value "LMV321L")
      (footprint "eagle-import:SOT23-5")
      (libsource (lib "eagle-import") (part "LMV321L"))
    )
    (comp (ref "U$24")
      (value "LMV321L")
      (footprint "eagle-import:SOT23-5")
      (libsource (lib "eagle-import") (part "LMV321L"))
    )
    (comp (ref "U$25")
      (value "BZT52C13")
      (footprint "eagle-import:SOD-123")
      (libsource (lib "eagle-import") (part "BZT52C"))
    )
    (comp (ref "U$26")
      (value "BZT52C13")
      (footprint "eagle-import:SOD-123")
      (libsource (lib "eagle-import") (part "BZT52C"))
    )
    (comp (ref "U$29")
      (value "BZT52C13")
      (footprint "eagle-import:SOD-123")
      (libsource (lib "eagle-import") (part "BZT52C"))
    )
    (comp (ref "U$32")
      (value "BZT52C5V6")
      (footprint "eagle-import:SOD-123")
      (libsource (lib "eagle-import") (part "BZT52C"))
    )
    (comp (ref "U$33")
      (value "BZT52C5V6")
      (footprint "eagle-import:SOD-123")
      (libsource (lib "eagle-import") (part "BZT52C"))
    )
    (comp (ref "U$34")
      (value "BZT52C5V6")
      (footprint "eagle-import:SOD-123")
      (libsource (lib "eagle-import") (part "BZT52C"))
    )
    (comp (ref "Q18")
      (value "DMN6140L-7")
      (footprint "eagle-import:SOT23")
      (libsource (lib "eagle-import") (part "DMN6140L-7"))
    )
    (comp (ref "Q20")
      (value "DMN6140L-7")
      (footprint "eagle-import:SOT23")
      (libsource (lib "eagle-import") (part "DMN6140L-7"))
    )
    (comp (ref "Q21")
      (value "DMN6140L-7")
      (footprint "eagle-import:SOT23")
      (libsource (lib "eagle-import") (part "DMN6140L-7"))
    )
    (comp (ref "R30")
      (value "10k")
      (footprint "eagle-import:R0603")
      (libsource (lib "eagle-import") (part "R-US_R0603"))
    )
    (comp (ref "R31")
      (value "10k")
      (footprint "eagle-import:R0603")
      (libsource (lib "eagle-import") (part "R-US_R0603"))
    )
    (comp (ref "R32")
      (value "10k")
      (footprint "eagle-import:R0603")
      (libsource (lib "eagle-import") (part "R-US_R0603"))
    )
    (comp (ref "R9")
      (value "1k")
      (footprint "eagle-import:R0603")
      (libsource (lib "eagle-import") (part "R-US_R0603"))
    )
    (comp (ref "U$4")
      (value "DNBT8105")
      (footprint "eagle-import:SOT23-3")
      (libsource (lib "eagle-import") (part "DNBT8105"))
    )
    (comp (ref "Q4")
      (value "DMN6140L-7")
      (footprint "eagle-import:SOT23")
      (libsource (lib "eagle-import") (part "DMN6140L-7"))
    )
    (comp (ref "C2")
      (value "10uF")
      (footprint "eagle-import:C0805")
      (libsource (lib "eagle-import") (part "C-USC0805"))
    )
    (comp (ref "C5")
      (value "0.1u")
      (footprint "eagle-import:C0603")
      (libsource (lib "eagle-import") (part "resistor_348_C-USC0603"))
    )
    (comp (ref "C6")
      (value "0.1u")
      (footprint "eagle-import:C0603")
      (libsource (lib "eagle-import") (part "resistor_348_C-USC0603"))
    )
    (comp (ref "C7")
      (value "0.1u")
      (footprint "eagle-import:C0603")
      (libsource (lib "eagle-import") (part "resistor_348_C-USC0603"))
    )
    (comp (ref "C8")
      (value "10uF")
      (footprint "eagle-import:C0805")
      (libsource (lib "eagle-import") (part "C-USC0805"))
    )
    (comp (ref "C9")
      (value "10uF")
      (footprint "eagle-import:C0805")
      (libsource (lib "eagle-import") (part "C-USC0805"))
    )
    (comp (ref "D1")
      (value "BLUE")
      (footprint "eagle-import:LED-0603")
      (libsource (lib "eagle-import") (part "LED-BLUE0603"))
    )
    (comp (ref "D2")
      (value "1N914")
      (footprint "eagle-import:SOD323-F")
      (libsource (lib "eagle-import") (part "1N914"))
    )
    (comp (ref "D4")
      (value "BLUE")
      (footprint "eagle-import:LED-0603")
      (libsource (lib "eagle-import") (part "LED-BLUE0603"))
    )
    (comp (ref "D7")
      (value "BLUE")
      (footprint "eagle-import:LED-0603")
      (libsource (lib "eagle-import") (part "LED-BLUE0603"))
    )
    (comp (ref "D9")
      (value "1N914")
      (footprint "eagle-import:SOD323-F")
      (libsource (lib "eagle-import") (part "1N914"))
    )
    (comp (ref "D15")
      (value "1N914")
      (footprint "eagle-import:SOD323-F")
      (libsource (lib "eagle-import") (part "1N914"))
    )
    (comp (ref "Q1")
      (value "DMN6140L-7")
      (footprint "eagle-import:SOT23")
      (libsource (lib "eagle-import") (part "DMN6140L-7"))
    )
    (comp (ref "Q2")
      (value "DMN6140L-7")
      (footprint "eagle-import:SOT23")
      (libsource (lib "eagle-import") (part "DMN6140L-7"))
    )
    (comp (ref "Q3")
      (value "DMN6140L-7")
      (footprint "eagle-import:SOT23")
      (libsource (lib "eagle-import") (part "DMN6140L-7"))
    )
    (comp (ref "Q5")
      (value "DMN6140L-7")
      (footprint "eagle-import:SOT23")
      (libsource (lib "eagle-import") (part "DMN6140L-7"))
    )
    (comp (ref "Q6")
      (value "DMP3099L-7")
      (footprint "eagle-import:SOT23")
      (libsource (lib "eagle-import") (part "DMP3099L-7"))
    )
    (comp (ref "Q9")
      (value "DMN6140L-7")
      (footprint "eagle-import:SOT23")
      (libsource (lib "eagle-import") (part "DMN6140L-7"))
    )
    (comp (ref "Q11")
      (value "DMP3099L-7")
      (footprint "eagle-import:SOT23")
      (libsource (lib "eagle-import") (part "DMP3099L-7"))
    )
    (comp (ref "Q15")
      (value "DMP3099L-7")
      (footprint "eagle-import:SOT23")
      (libsource (lib "eagle-import") (part "DMP3099L-7"))
    )
    (comp (ref "Q16")
      (value "DMN6140L-7")
      (footprint "eagle-import:SOT23")
      (libsource (lib "eagle-import") (part "DMN6140L-7"))
    )
    (comp (ref "R12")
      (value "10k")
      (footprint "eagle-import:R0603")
      (libsource (lib "eagle-import") (part "resistor_348_R-US_R0603"))
    )
    (comp (ref "R13")
      (value "10k")
      (footprint "eagle-import:R0603")
      (libsource (lib "eagle-import") (part "resistor_348_R-US_R0603"))
    )
    (comp (ref "R14")
      (value "10k")
      (footprint "eagle-import:R0603")
      (libsource (lib "eagle-import") (part "resistor_348_R-US_R0603"))
    )
    (comp (ref "R15")
      (value "900")
      (footprint "eagle-import:R0603")
      (libsource (lib "eagle-import") (part "resistor_348_R-US_R0603"))
    )
    (comp (ref "R16")
      (value "10k")
      (footprint "eagle-import:R0603")
      (libsource (lib "eagle-import") (part "resistor_348_R-US_R0603"))
    )
    (comp (ref "R17")
      (value "10k")
      (footprint "eagle-import:R0603")
      (libsource (lib "eagle-import") (part "resistor_348_R-US_R0603"))
    )
    (comp (ref "R18")
      (value "10k")
      (footprint "eagle-import:R0603")
      (libsource (lib "eagle-import") (part "resistor_348_R-US_R0603"))
    )
    (comp (ref "R21")
      (value "900")
      (footprint "eagle-import:R0603")
      (libsource (lib "eagle-import") (part "resistor_348_R-US_R0603"))
    )
    (comp (ref "R22")
      (value "900")
      (footprint "eagle-import:R0603")
      (libsource (lib "eagle-import") (part "resistor_348_R-US_R0603"))
    )
    (comp (ref "R25")
      (value "1k")
      (footprint "eagle-import:R0603")
      (libsource (lib "eagle-import") (part "resistor_348_R-US_R0603"))
    )
    (comp (ref "U$13")
      (value "EC2")
      (footprint "eagle-import:DPDT_2.54")
      (libsource (lib "eagle-import") (part "EC2"))
    )
    (comp (ref "U$14")
      (value "EC2")
      (footprint "eagle-import:DPDT_2.54")
      (libsource (lib "eagle-import") (part "EC2"))
    )
    (comp (ref "U$15")
      (value "EC2")
      (footprint "eagle-import:DPDT_2.54")
      (libsource (lib "eagle-import") (part "EC2"))
    )
    (comp (ref "C16")
      (value "1u")
      (footprint "eagle-import:C0805")
      (libsource (lib "eagle-import") (part "C-USC0805"))
    )
    (comp (ref "C20")
      (value "1u")
      (footprint "eagle-import:C0805")
      (libsource (lib "eagle-import") (part "C-USC0805"))
    )
    (comp (ref "C21")
      (value "1u")
      (footprint "eagle-import:C0603")
      (libsource (lib "eagle-import") (part "C-USC0603"))
    )
    (comp (ref "C33")
      (value "0.001u")
      (footprint "eagle-import:C0805")
      (libsource (lib "eagle-import") (part "C-USC0805"))
    )
    (comp (ref "C34")
      (value "0.001u")
      (footprint "eagle-import:C0805")
      (libsource (lib "eagle-import") (part "C-USC0805"))
    )
    (comp (ref "C35")
      (value "0.001u")
      (footprint "eagle-import:C0805")
      (libsource (lib "eagle-import") (part "C-USC0805"))
    )
    (comp (ref "C36")
      (value "0.001u")
      (footprint "eagle-import:C0805")
      (libsource (lib "eagle-import") (part "C-USC0805"))
    )
    (comp (ref "D13")
      (value "RED")
      (footprint "eagle-import:LED-0603")
      (libsource (lib "eagle-import") (part "LED-RED0603"))
    )
    (comp (ref "JP2")
      (value "PINHD-1X5")
      (footprint "eagle-import:1X05")
      (libsource (lib "eagle-import") (part "PINHD-1X5"))
    )
    (comp (ref "R7")
      (value "50k")
      (footprint "eagle-import:R0603")
      (libsource (lib "eagle-import") (part "R-US_R0603"))
    )
    (comp (ref "R28")
      (value "10k")
      (footprint "eagle-import:R0603")
      (libsource (lib "eagle-import") (part "R-US_R0603"))
    )
    (comp (ref "R29")
      (value "10k")
      (footprint "eagle-import:R0603")
      (libsource (lib "eagle-import") (part "R-US_R0603"))
    )
    (comp (ref "R47")
      (value "10k")
      (footprint "eagle-import:R0603")
      (libsource (lib "eagle-import") (part "R-US_R0603"))
    )
    (comp (ref "R48")
      (value "10k")
      (footprint "eagle-import:R0603")
      (libsource (lib "eagle-import") (part "R-US_R0603"))
    )
    (comp (ref "R57")
      (value "10")
      (footprint "eagle-import:R0603")
      (libsource (lib "eagle-import") (part "R-US_R0603"))
    )
    (comp (ref "R58")
      (value "10k")
      (footprint "eagle-import:R0603")
      (libsource (lib "eagle-import") (part "R-US_R0603"))
    )
    (comp (ref "R59")
      (value "10")
      (footprint "eagle-import:R0603")
      (libsource (lib "eagle-import") (part "R-US_R0603"))
    )
    (comp (ref "R60")
      (value "10k")
      (footprint "eagle-import:R0603")
      (libsource (lib "eagle-import") (part "R-US_R0603"))
    )
    (comp (ref "R61")
      (value "10")
      (footprint "eagle-import:R0603")
      (libsource (lib "eagle-import") (part "R-US_R0603"))
    )
    (comp (ref "R62")
      (value "10k")
      (footprint "eagle-import:R0603")
      (libsource (lib "eagle-import") (part "R-US_R0603"))
    )
    (comp (ref "R63")
      (value "10")
      (footprint "eagle-import:R0603")
      (libsource (lib "eagle-import") (part "R-US_R0603"))
    )
    (comp (ref "R64")
      (value "10k")
      (footprint "eagle-import:R0603")
      (libsource (lib "eagle-import") (part "R-US_R0603"))
    )
    (comp (ref "R65")
      (value "1k")
      (footprint "eagle-import:R0603")
      (libsource (lib "eagle-import") (part "R-US_R0603"))
    )
    (comp (ref "R66")
      (value "1k")
      (footprint "eagle-import:R0603")
      (libsource (lib "eagle-import") (part "R-US_R0603"))
    )
    (comp (ref "R67")
      (value "1k")
      (footprint "eagle-import:R0603")
      (libsource (lib "eagle-import") (part "R-US_R0603"))
    )
    (comp (ref "R68")
      (value "1k")
      (footprint "eagle-import:R0603")
      (libsource (lib "eagle-import") (part "R-US_R0603"))
    )
    (comp (ref "U$12")
      (value "MCP4018")
      (footprint "eagle-import:SOT23-6")
      (libsource (lib "eagle-import") (part "MCP4018"))
    )
    (comp (ref "U$18")
      (value "LMV321L")
      (footprint "eagle-import:SOT23-5")
      (libsource (lib "eagle-import") (part "LMV321L"))
    )
    (comp (ref "U$36")
      (value "BZT52C5V6")
      (footprint "eagle-import:SOD-123")
      (libsource (lib "eagle-import") (part "BZT52C"))
    )
    (comp (ref "U$37")
      (value "BZT52C5V6")
      (footprint "eagle-import:SOD-123")
      (libsource (lib "eagle-import") (part "BZT52C"))
    )
    (comp (ref "U$38")
      (value "BZT52C5V6")
      (footprint "eagle-import:SOD-123")
      (libsource (lib "eagle-import") (part "BZT52C"))
    )
    (comp (ref "U$39")
      (value "BZT52C5V6")
      (footprint "eagle-import:SOD-123")
      (libsource (lib "eagle-import") (part "BZT52C"))
    )
    (comp (ref "U2")
      (value "STM32F103CBT6")
      (footprint "eagle-import:QFP50P900X900X160-48N")
      (libsource (lib "eagle-import") (part "STM32F103CBT6"))
    )
    (comp (ref "Q10")
      (value "DMN6140L-7")
      (footprint "eagle-import:SOT23")
      (libsource (lib "eagle-import") (part "DMN6140L-7"))
    )
    (comp (ref "R3")
      (value "3.6k")
      (footprint "eagle-import:R0603")
      (libsource (lib "eagle-import") (part "R-US_R0603"))
    )
    (comp (ref "R6")
      (value "3.6k")
      (footprint "eagle-import:R0603")
      (libsource (lib "eagle-import") (part "R-US_R0603"))
    )
    (comp (ref "R23")
      (value "10k")
      (footprint "eagle-import:R0603")
      (libsource (lib "eagle-import") (part "resistor_348_R-US_R0603"))
    )
    (comp (ref "U$7")
      (value "DNBT8105")
      (footprint "eagle-import:SOT23-3")
      (libsource (lib "eagle-import") (part "DNBT8105"))
    )
    (comp (ref "U$8")
      (value "DNBT8105")
      (footprint "eagle-import:SOT23-3")
      (libsource (lib "eagle-import") (part "DNBT8105"))
    )
    (comp (ref "BRAKE")
      (value "PV36")
      (footprint "eagle-import:PV36")
      (libsource (lib "eagle-import") (part "PV36"))
    )
    (comp (ref "BTH1")
      (value "TPTP09R")
      (footprint "eagle-import:TP09R")
      (libsource (lib "eagle-import") (part "TPTP09R"))
    )
    (comp (ref "C1")
      (value "0.1u")
      (footprint "eagle-import:C0603")
      (libsource (lib "eagle-import") (part "resistor_348_C-USC0603"))
    )
    (comp (ref "C3")
      (value "3u")
      (footprint "eagle-import:C0603")
      (libsource (lib "eagle-import") (part "resistor_348_C-USC0603"))
    )
    (comp (ref "C4")
      (value "3u")
      (footprint "eagle-import:C0603")
      (libsource (lib "eagle-import") (part "resistor_348_C-USC0603"))
    )
    (comp (ref "C24")
      (value "0.1u")
      (footprint "eagle-import:C0603")
      (libsource (lib "eagle-import") (part "resistor_348_C-USC0603"))
    )
    (comp (ref "C25")
      (value "0.01u")
      (footprint "eagle-import:C0603")
      (libsource (lib "eagle-import") (part "resistor_348_C-USC0603"))
    )
    (comp (ref "C27")
      (value "0.1u")
      (footprint "eagle-import:C0603")
      (libsource (lib "eagle-import") (part "resistor_348_C-USC0603"))
    )
    (comp (ref "C28")
      (value "0.1u")
      (footprint "eagle-import:C0603")
      (libsource (lib "eagle-import") (part "resistor_348_C-USC0603"))
    )
    (comp (ref "CURR")
      (value "PV36")
      (footprint "eagle-import:PV36")
      (libsource (lib "eagle-import") (part "PV36"))
    )
    (comp (ref "Q12")
      (value "IRLML6346PBF")
      (footprint "eagle-import:SOT23")
      (libsource (lib "eagle-import") (part "IRLML6346PBF"))
    )
    (comp (ref "Q13")
      (value "IRLML6346PBF")
      (footprint "eagle-import:SOT23")
      (libsource (lib "eagle-import") (part "IRLML6346PBF"))
    )
    (comp (ref "Q14")
      (value "IRLML6346PBF")
      (footprint "eagle-import:SOT23")
      (libsource (lib "eagle-import") (part "IRLML6346PBF"))
    )
    (comp (ref "Q17")
      (value "IRLML6346PBF")
      (footprint "eagle-import:SOT23")
      (libsource (lib "eagle-import") (part "IRLML6346PBF"))
    )
    (comp (ref "R1")
      (value "100k")
      (footprint "eagle-import:R0603")
      (libsource (lib "eagle-import") (part "resistor_348_R-US_R0603"))
    )
    (comp (ref "R5")
      (value "10k")
      (footprint "eagle-import:R0603")
      (libsource (lib "eagle-import") (part "resistor_348_R-US_R0603"))
    )
    (comp (ref "R8")
      (value "10k")
      (footprint "eagle-import:R0603")
      (libsource (lib "eagle-import") (part "resistor_348_R-US_R0603"))
    )
    (comp (ref "R11")
      (value "1k")
      (footprint "eagle-import:R0603")
      (libsource (lib "eagle-import") (part "resistor_348_R-US_R0603"))
    )
    (comp (ref "R36")
      (value "100k")
      (footprint "eagle-import:R0603")
      (libsource (lib "eagle-import") (part "resistor_348_R-US_R0603"))
    )
    (comp (ref "R39")
      (value "10k")
      (footprint "eagle-import:R0603")
      (libsource (lib "eagle-import") (part "resistor_348_R-US_R0603"))
    )
    (comp (ref "R40")
      (value "1k")
      (footprint "eagle-import:R0603")
      (libsource (lib "eagle-import") (part "resistor_348_R-US_R0603"))
    )
    (comp (ref "R43")
      (value "10k")
      (footprint "eagle-import:R0603")
      (libsource (lib "eagle-import") (part "resistor_348_R-US_R0603"))
    )
    (comp (ref "R44")
      (value "1k")
      (footprint "eagle-import:R0603")
      (libsource (lib "eagle-import") (part "resistor_348_R-US_R0603"))
    )
    (comp (ref "TTH1")
      (value "TPTP09R")
      (footprint "eagle-import:TP09R")
      (libsource (lib "eagle-import") (part "TPTP09R"))
    )
    (comp (ref "U$5")
      (value "TS881")
      (footprint "eagle-import:SOT23-5")
      (libsource (lib "eagle-import") (part "TS881"))
    )
    (comp (ref "U$16")
      (value "TS881")
      (footprint "eagle-import:SOT23-5")
      (libsource (lib "eagle-import") (part "TS881"))
    )
    (comp (ref "U$17")
      (value "TS881")
      (footprint "eagle-import:SOT23-5")
      (libsource (lib "eagle-import") (part "TS881"))
    )
    (comp (ref "U$20")
      (value "TS881")
      (footprint "eagle-import:SOT23-5")
      (libsource (lib "eagle-import") (part "TS881"))
    )
  )
  (nets
    (net (code "1") (name "+3V3") (class "Default")
      (node (ref "C11") (pin "1") (pinfunction "1_1") (pintype "passive"))
      (node (ref "C15") (pin "1") (pinfunction "1_1") (pintype "passive"))
      (node (ref "C16") (pin "1") (pinfunction "1_1") (pintype "passive"))
      (node (ref "C19") (pin "1") (pinfunction "1_1") (pintype "passive"))
      (node (ref "C20") (pin "1") (pinfunction "1_1") (pintype "passive"))
      (node (ref "D11") (pin "A") (pinfunction "A_A") (pintype "passive"))
      (node (ref "JP1") (pin "1") (pinfunction "1_1") (pintype "passive"))
      (node (ref "JP2") (pin "1") (pinfunction "1_1") (pintype "passive"))
      (node (ref "R12") (pin "2") (pinfunction "2_2") (pintype "passive"))
      (node (ref "R13") (pin "2") (pinfunction "2_2") (pintype "passive"))
      (node (ref "R14") (pin "2") (pinfunction "2_2") (pintype "passive"))
      (node (ref "R23") (pin "2") (pinfunction "2_2") (pintype "passive"))
      (node (ref "R26") (pin "1") (pinfunction "1_1") (pintype "passive"))
      (node (ref "R27") (pin "1") (pinfunction "1_1") (pintype "passive"))
      (node (ref "R28") (pin "1") (pinfunction "1_1") (pintype "passive"))
      (node (ref "R29") (pin "1") (pinfunction "1_1") (pintype "passive"))
      (node (ref "R74") (pin "2") (pinfunction "2_2") (pintype "passive"))
      (node (ref "U$11") (pin "5") (pinfunction "VIO_5") (pintype "bidirectional"))
      (node (ref "U$9") (pin "2") (pinfunction "VOUT_2") (pintype "output"))
      (node (ref "U$9") (pin "4") (pinfunction "VOUT_4") (pintype "output"))
      (node (ref "U1") (pin "24") (pinfunction "VDD_1_24") (pintype "bidirectional"))
      (node (ref "U1") (pin "36") (pinfunction "VDD_2_36") (pintype "power_in"))
      (node (ref "U1") (pin "48") (pinfunction "VDD_3_48") (pintype "power_in"))
      (node (ref "U1") (pin "9") (pinfunction "VDDA_9") (pintype "power_in"))
      (node (ref "U2") (pin "24") (pinfunction "VDD_1_24") (pintype "bidirectional"))
      (node (ref "U2") (pin "36") (pinfunction "VDD_2_36") (pintype "power_in"))
      (node (ref "U2") (pin "48") (pinfunction "VDD_3_48") (pintype "power_in"))
      (node (ref "U2") (pin "9") (pinfunction "VDDA_9") (pintype "power_in"))
    )
    (net (code "2") (name "+5V") (class "Default")
      (node (ref "BRAKE") (pin "A") (pinfunction "A_A") (pintype "passive"))
      (node (ref "C1") (pin "1") (pinfunction "1_1") (pintype "passive"))
      (node (ref "C14") (pin "1") (pinfunction "1_1") (pintype "passive"))
      (node (ref "C21") (pin "1") (pinfunction "1_1") (pintype "passive"))
      (node (ref "C24") (pin "1") (pinfunction "1_1") (pintype "passive"))
      (node (ref "C27") (pin "1") (pinfunction "1_1") (pintype "passive"))
      (node (ref "C28") (pin "1") (pinfunction "1_1") (pintype "passive"))
      (node (ref "C37") (pin "1") (pinfunction "1_1") (pintype "passive"))
      (node (ref "C38") (pin "1") (pinfunction "1_1") (pintype "passive"))
      (node (ref "C39") (pin "1") (pinfunction "1_1") (pintype "passive"))
      (node (ref "CURR") (pin "A") (pinfunction "A_A") (pintype "passive"))
      (node (ref "CURRENT_SENSOR_SUPPLY") (pin "1") (pinfunction "1_1") (pintype "passive"))
      (node (ref "D12") (pin "A") (pinfunction "A_A") (pintype "passive"))
      (node (ref "R11") (pin "2") (pinfunction "2_2") (pintype "passive"))
      (node (ref "R35") (pin "2") (pinfunction "2_2") (pintype "passive"))
      (node (ref "R39") (pin "2") (pinfunction "2_2") (pintype "passive"))
      (node (ref "R47") (pin "1") (pinfunction "1_1") (pintype "passive"))
      (node (ref "R48") (pin "1") (pinfunction "1_1") (pintype "passive"))
      (node (ref "R65") (pin "2") (pinfunction "2_2") (pintype "passive"))
      (node (ref "R66") (pin "2") (pinfunction "2_2") (pintype "passive"))
      (node (ref "R67") (pin "2") (pinfunction "2_2") (pintype "passive"))
      (node (ref "R68") (pin "2") (pinfunction "2_2") (pintype "passive"))
      (node (ref "R8") (pin "2") (pinfunction "2_2") (pintype "passive"))
      (node (ref "TSAL_EN") (pin "1") (pinfunction "1_1") (pintype "passive"))
      (node (ref "U$10") (pin "2") (pinfunction "VOUT_2") (pintype "output"))
      (node (ref "U$10") (pin "4") (pinfunction "VOUT_4") (pintype "output"))
      (node (ref "U$11") (pin "3") (pinfunction "VDD_3") (pintype "bidirectional"))
      (node (ref "U$12") (pin "1") (pinfunction "VDD_1") (pintype "passive"))
      (node (ref "U$16") (pin "5") (pinfunction "VDD_5") (pintype "bidirectional"))
      (node (ref "U$17") (pin "5") (pinfunction "VDD_5") (pintype "bidirectional"))
      (node (ref "U$18") (pin "5") (pinfunction "VDD_5") (pintype "bidirectional"))
      (node (ref "U$20") (pin "5") (pinfunction "VDD_5") (pintype "bidirectional"))
      (node (ref "U$22") (pin "5") (pinfunction "VDD_5") (pintype "bidirectional"))
      (node (ref "U$23") (pin "5") (pinfunction "VDD_5") (pintype "bidirectional"))
      (node (ref "U$24") (pin "5") (pinfunction "VDD_5") (pintype "bidirectional"))
      (node (ref "U$5") (pin "5") (pinfunction "VDD_5") (pintype "bidirectional"))
    )
    (net (code "3") (name "+12V") (class "Default")
      (node (ref "C10") (pin "+") (pinfunction "+_+") (pintype "passive"))
      (node (ref "C12") (pin "1") (pinfunction "1_1") (pintype "passive"))
      (node (ref "C13") (pin "1") (pinfunction "1_1") (pintype "passive"))
      (node (ref "L4") (pin "P$2") (pinfunction "2_P$2") (pintype "passive"))
      (node (ref "Q11") (pin "2") (pinfunction "S_2") (pintype "passive"))
      (node (ref "Q15") (pin "2") (pinfunction "S_2") (pintype "passive"))
      (node (ref "Q6") (pin "2") (pinfunction "S_2") (pintype "passive"))
      (node (ref "R25") (pin "2") (pinfunction "2_2") (pintype "passive"))
      (node (ref "R5") (pin "2") (pinfunction "2_2") (pintype "passive"))
      (node (ref "U$10") (pin "3") (pinfunction "VIN_3") (pintype "input"))
      (node (ref "U$13") (pin "$P5") (pinfunction "$P5_$P5") (pintype "passive"))
      (node (ref "U$14") (pin "$P5") (pinfunction "$P5_$P5") (pintype "passive"))
      (node (ref "U$15") (pin "$P5") (pinfunction "$P5_$P5") (pintype "passive"))
      (node (ref "U$9") (pin "3") (pinfunction "VIN_3") (pintype "input"))
    )
    (net (code "4") (name "AIR_IN") (class "Default")
      (node (ref "AIR") (pin "1") (pinfunction "1_1") (pintype "passive"))
      (node (ref "U$13") (pin "$P9") (pinfunction "$P9_$P9") (pintype "passive"))
    )
    (net (code "5") (name "AIR_OUT") (class "Default")
      (node (ref "AIR") (pin "2") (pinfunction "2_2") (pintype "passive"))
      (node (ref "U$15") (pin "$P8") (pinfunction "$P8_$P8") (pintype "passive"))
    )
    (net (code "6") (name "APPS_EN") (class "Default")
      (node (ref "Q20") (pin "1") (pinfunction "G_1") (pintype "passive"))
      (node (ref "R30") (pin "2") (pinfunction "2_2") (pintype "passive"))
      (node (ref "U1") (pin "40") (pinfunction "PB4_40") (pintype "bidirectional"))
    )
    (net (code "7") (name "BRAKE_LIGHT-") (class "Default")
      (node (ref "DRIVERS") (pin "1") (pinfunction "1_1") (pintype "passive"))
      (node (ref "U$4") (pin "3") (pinfunction "C_3") (pintype "passive"))
    )
    (net (code "8") (name "BRAKE_LIGHT_EN") (class "Default")
      (node (ref "R9") (pin "1") (pinfunction "1_1") (pintype "passive"))
      (node (ref "U1") (pin "26") (pinfunction "PB13_26") (pintype "bidirectional"))
    )
    (net (code "9") (name "BRAKE_PRESSURE") (class "Default")
      (node (ref "FAULT_INPUT") (pin "4") (pinfunction "4_4") (pintype "passive"))
      (node (ref "R53") (pin "1") (pinfunction "1_1") (pintype "passive"))
    )
    (net (code "10") (name "BRAKE_PRESSURE_F") (class "Default")
      (node (ref "R70") (pin "2") (pinfunction "2_2") (pintype "passive"))
      (node (ref "U$24") (pin "3") (pinfunction "-IN_3") (pintype "input"))
      (node (ref "U$24") (pin "4") (pinfunction "OUT_4") (pintype "output"))
      (node (ref "U$5") (pin "3") (pinfunction "+IN_3") (pintype "input"))
    )
    (net (code "11") (name "BRAKE_PRESSURE_F_3_3") (class "Default")
      (node (ref "R70") (pin "1") (pinfunction "1_1") (pintype "passive"))
      (node (ref "R71") (pin "2") (pinfunction "2_2") (pintype "passive"))
      (node (ref "U1") (pin "10") (pinfunction "PA0-WKUP_10") (pintype "bidirectional"))
    )
    (net (code "12") (name "BRAKE_TH") (class "Default")
      (node (ref "BRAKE") (pin "W") (pinfunction "W_W") (pintype "bidirectional"))
      (node (ref "BTH1") (pin "TP") (pinfunction "TP_TP") (pintype "input"))
      (node (ref "U$5") (pin "4") (pinfunction "-IN_4") (pintype "input"))
    )
    (net (code "13") (name "BSPD_BRAKE_COND") (class "Default")
      (node (ref "C3") (pin "1") (pinfunction "1_1") (pintype "passive"))
      (node (ref "Q13") (pin "1") (pinfunction "G_1") (pintype "passive"))
      (node (ref "R1") (pin "1") (pinfunction "1_1") (pintype "passive"))
    )
    (net (code "14") (name "BSPD_CURR_COND") (class "Default")
      (node (ref "C4") (pin "1") (pinfunction "1_1") (pintype "passive"))
      (node (ref "Q12") (pin "1") (pinfunction "G_1") (pintype "passive"))
      (node (ref "R36") (pin "1") (pinfunction "1_1") (pintype "passive"))
    )
    (net (code "15") (name "BSPD_OC") (class "Default")
      (node (ref "Q17") (pin "1") (pinfunction "G_1") (pintype "passive"))
      (node (ref "U$17") (pin "1") (pinfunction "OUT_1") (pintype "output"))
    )
    (net (code "16") (name "BSPD_SC") (class "Default")
      (node (ref "Q14") (pin "1") (pinfunction "G_1") (pintype "passive"))
      (node (ref "U$16") (pin "1") (pinfunction "OUT_1") (pintype "output"))
    )
    (net (code "17") (name "BTSF_EN") (class "Default")
      (node (ref "Q18") (pin "1") (pinfunction "G_1") (pintype "passive"))
      (node (ref "R31") (pin "2") (pinfunction "2_2") (pintype "passive"))
      (node (ref "U1") (pin "41") (pinfunction "PB5_41") (pintype "bidirectional"))
    )
    (net (code "18") (name "CANH") (class "Default")
      (node (ref "CAN") (pin "2") (pinfunction "2_2") (pintype "passive"))
      (node (ref "D8") (pin "1") (pinfunction "1_1") (pintype "passive"))
      (node (ref "R20") (pin "2") (pinfunction "2_2") (pintype "passive"))
      (node (ref "R24") (pin "2") (pinfunction "2_2") (pintype "passive"))
      (node (ref "U$11") (pin "7") (pinfunction "CANH_7") (pintype "bidirectional"))
    )
    (net (code "19") (name "CANL") (class "Default")
      (node (ref "CAN") (pin "1") (pinfunction "1_1") (pintype "passive"))
      (node (ref "D8") (pin "2") (pinfunction "2_2") (pintype "passive"))
      (node (ref "R19") (pin "2") (pinfunction "2_2") (pintype "passive"))
      (node (ref "R24") (pin "1") (pinfunction "1_1") (pintype "passive"))
      (node (ref "U$11") (pin "6") (pinfunction "CANL_6") (pintype "bidirectional"))
    )
    (net (code "20") (name "CAN_RX") (class "Default")
      (node (ref "U$11") (pin "4") (pinfunction "RX_4") (pintype "bidirectional"))
      (node (ref "U1") (pin "32") (pinfunction "PA11_32") (pintype "power_in"))
    )
    (net (code "21") (name "CAN_STBY") (class "Default")
      (node (ref "U$11") (pin "8") (pinfunction "STBY_8") (pintype "bidirectional"))
      (node (ref "U1") (pin "31") (pinfunction "PA10_31") (pintype "bidirectional"))
    )
    (net (code "22") (name "CAN_TX") (class "Default")
      (node (ref "U$11") (pin "1") (pinfunction "TX_1") (pintype "bidirectional"))
      (node (ref "U1") (pin "33") (pinfunction "PA12_33") (pintype "bidirectional"))
    )
    (net (code "23") (name "CURRENT_SENSE") (class "Default")
      (node (ref "FAULT_INPUT") (pin "2") (pinfunction "2_2") (pintype "passive"))
      (node (ref "R44") (pin "2") (pinfunction "2_2") (pintype "passive"))
      (node (ref "R8") (pin "1") (pinfunction "1_1") (pintype "passive"))
    )
    (net (code "24") (name "CURRENT_SENSE_F") (class "Default")
      (node (ref "C25") (pin "1") (pinfunction "1_1") (pintype "passive"))
      (node (ref "R44") (pin "1") (pinfunction "1_1") (pintype "passive"))
      (node (ref "U$16") (pin "4") (pinfunction "-IN_4") (pintype "input"))
      (node (ref "U$17") (pin "3") (pinfunction "+IN_3") (pintype "input"))
      (node (ref "U$20") (pin "3") (pinfunction "+IN_3") (pintype "input"))
    )
    (net (code "25") (name "CURR_TH") (class "Default")
      (node (ref "CURR") (pin "W") (pinfunction "W_W") (pintype "bidirectional"))
      (node (ref "TTH1") (pin "TP") (pinfunction "TP_TP") (pintype "input"))
      (node (ref "U$20") (pin "4") (pinfunction "-IN_4") (pintype "input"))
    )
    (net (code "26") (name "DEBUG") (class "Default")
      (node (ref "D10") (pin "C") (pinfunction "C_C") (pintype "passive"))
      (node (ref "U1") (pin "2") (pinfunction "PC13-TAMPER-RTC_2") (pintype "bidirectional"))
    )
    (net (code "27") (name "DEBUG_TC") (class "Default")
      (node (ref "D13") (pin "C") (pinfunction "C_C") (pintype "passive"))
      (node (ref "U2") (pin "2") (pinfunction "PC13-TAMPER-RTC_2") (pintype "bidirectional"))
    )
    (net (code "28") (name "ENABLE_IN") (class "Default")
      (node (ref "ENABLE") (pin "1") (pinfunction "1_1") (pintype "passive"))
      (node (ref "Q21") (pin "2") (pinfunction "S_2") (pintype "passive"))
    )
    (net (code "29") (name "ENABLE_OUT") (class "Default")
      (node (ref "ENABLE") (pin "2") (pinfunction "2_2") (pintype "passive"))
      (node (ref "Q20") (pin "3") (pinfunction "D_3") (pintype "passive"))
    )
    (net (code "30") (name "FAULT_BMS") (class "Default")
      (node (ref "FAULT_INPUT") (pin "1") (pinfunction "1_1") (pintype "passive"))
      (node (ref "R37") (pin "1") (pinfunction "1_1") (pintype "passive"))
    )
    (net (code "31") (name "FAULT_BMS_F") (class "Default")
      (node (ref "C23") (pin "1") (pinfunction "1_1") (pintype "passive"))
      (node (ref "C6") (pin "1") (pinfunction "1_1") (pintype "passive"))
      (node (ref "Q3") (pin "1") (pinfunction "G_1") (pintype "passive"))
      (node (ref "R17") (pin "2") (pinfunction "2_2") (pintype "passive"))
      (node (ref "R38") (pin "2") (pinfunction "2_2") (pintype "passive"))
    )
    (net (code "32") (name "FAULT_BMS_STAT") (class "Default")
      (node (ref "C8") (pin "1") (pinfunction "1_1") (pintype "passive"))
      (node (ref "D9") (pin "C") (pinfunction "C_C") (pintype "passive"))
      (node (ref "Q2") (pin "1") (pinfunction "G_1") (pintype "passive"))
      (node (ref "R22") (pin "1") (pinfunction "1_1") (pintype "passive"))
      (node (ref "U$14") (pin "$P1") (pinfunction "$P1_$P1") (pintype "bidirectional"))
      (node (ref "U$14") (pin "$P4") (pinfunction "$P4_$P4") (pintype "passive"))
    )
    (net (code "33") (name "FAULT_BMS_STATUS_3_3") (class "Default")
      (node (ref "Q2") (pin "3") (pinfunction "D_3") (pintype "passive"))
      (node (ref "R13") (pin "1") (pinfunction "1_1") (pintype "passive"))
      (node (ref "U1") (pin "12") (pinfunction "PA2_12") (pintype "bidirectional"))
    )
    (net (code "34") (name "FAULT_BSPD") (class "Default")
      (node (ref "C7") (pin "1") (pinfunction "1_1") (pintype "passive"))
      (node (ref "Q12") (pin "3") (pinfunction "D_3") (pintype "passive"))
      (node (ref "Q14") (pin "3") (pinfunction "D_3") (pintype "passive"))
      (node (ref "Q17") (pin "3") (pinfunction "D_3") (pintype "passive"))
      (node (ref "Q5") (pin "1") (pinfunction "G_1") (pintype "passive"))
      (node (ref "R16") (pin "2") (pinfunction "2_2") (pintype "passive"))
      (node (ref "R5") (pin "1") (pinfunction "1_1") (pintype "passive"))
    )
    (net (code "35") (name "FAULT_BSPD_STAT") (class "Default")
      (node (ref "C2") (pin "1") (pinfunction "1_1") (pintype "passive"))
      (node (ref "D2") (pin "C") (pinfunction "C_C") (pintype "passive"))
      (node (ref "Q1") (pin "1") (pinfunction "G_1") (pintype "passive"))
      (node (ref "R15") (pin "1") (pinfunction "1_1") (pintype "passive"))
      (node (ref "U$13") (pin "$P1") (pinfunction "$P1_$P1") (pintype "bidirectional"))
      (node (ref "U$13") (pin "$P4") (pinfunction "$P4_$P4") (pintype "passive"))
    )
    (net (code "36") (name "FAULT_BSPD_STATUS_3_3") (class "Default")
      (node (ref "Q1") (pin "3") (pinfunction "D_3") (pintype "passive"))
      (node (ref "R12") (pin "1") (pinfunction "1_1") (pintype "passive"))
      (node (ref "U1") (pin "27") (pinfunction "PB14_27") (pintype "bidirectional"))
    )
    (net (code "37") (name "FAULT_IMD") (class "Default")
      (node (ref "FAULT_INPUT") (pin "3") (pinfunction "3_3") (pintype "passive"))
      (node (ref "R41") (pin "1") (pinfunction "1_1") (pintype "passive"))
    )
    (net (code "38") (name "FAULT_IMD_F") (class "Default")
      (node (ref "C26") (pin "1") (pinfunction "1_1") (pintype "passive"))
      (node (ref "C5") (pin "1") (pinfunction "1_1") (pintype "passive"))
      (node (ref "Q16") (pin "1") (pinfunction "G_1") (pintype "passive"))
      (node (ref "R18") (pin "2") (pinfunction "2_2") (pintype "passive"))
      (node (ref "R42") (pin "2") (pinfunction "2_2") (pintype "passive"))
    )
    (net (code "39") (name "FAULT_IMD_STAT") (class "Default")
      (node (ref "C9") (pin "1") (pinfunction "1_1") (pintype "passive"))
      (node (ref "D15") (pin "C") (pinfunction "C_C") (pintype "passive"))
      (node (ref "Q9") (pin "1") (pinfunction "G_1") (pintype "passive"))
      (node (ref "R21") (pin "1") (pinfunction "1_1") (pintype "passive"))
      (node (ref "U$15") (pin "$P1") (pinfunction "$P1_$P1") (pintype "bidirectional"))
      (node (ref "U$15") (pin "$P4") (pinfunction "$P4_$P4") (pintype "passive"))
    )
    (net (code "40") (name "FAULT_IMD_STATUS_3_3") (class "Default")
      (node (ref "Q9") (pin "3") (pinfunction "D_3") (pintype "passive"))
      (node (ref "R14") (pin "1") (pinfunction "1_1") (pintype "passive"))
      (node (ref "U1") (pin "13") (pinfunction "PA3_13") (pintype "bidirectional"))
    )
    (net (code "41") (name "FAULT_RESET") (class "Default")
      (node (ref "R33") (pin "1") (pinfunction "1_1") (pintype "passive"))
      (node (ref "TSAL_EN") (pin "4") (pinfunction "4_4") (pintype "passive"))
    )
    (net (code "42") (name "FAULT_RESET_F") (class "Default")
      (node (ref "C22") (pin "1") (pinfunction "1_1") (pintype "passive"))
      (node (ref "Q11") (pin "1") (pinfunction "G_1") (pintype "passive"))
      (node (ref "Q15") (pin "1") (pinfunction "G_1") (pintype "passive"))
      (node (ref "Q6") (pin "1") (pinfunction "G_1") (pintype "passive"))
      (node (ref "R25") (pin "1") (pinfunction "1_1") (pintype "passive"))
      (node (ref "R34") (pin "2") (pinfunction "2_2") (pintype "passive"))
    )
    (net (code "43") (name "GND") (class "Default")
      (node (ref "BRAKE") (pin "B") (pinfunction "B_B") (pintype "passive"))
      (node (ref "C1") (pin "2") (pinfunction "2_2") (pintype "passive"))
      (node (ref "C10") (pin "-") (pinfunction "-_-") (pintype "passive"))
      (node (ref "C11") (pin "2") (pinfunction "2_2") (pintype "passive"))
      (node (ref "C12") (pin "2") (pinfunction "2_2") (pintype "passive"))
      (node (ref "C13") (pin "2") (pinfunction "2_2") (pintype "passive"))
      (node (ref "C14") (pin "2") (pinfunction "2_2") (pintype "passive"))
      (node (ref "C15") (pin "2") (pinfunction "2_2") (pintype "passive"))
      (node (ref "C16") (pin "2") (pinfunction "2_2") (pintype "passive"))
      (node (ref "C17") (pin "2") (pinfunction "2_2") (pintype "passive"))
      (node (ref "C18") (pin "2") (pinfunction "2_2") (pintype "passive"))
      (node (ref "C19") (pin "2") (pinfunction "2_2") (pintype "passive"))
      (node (ref "C2") (pin "2") (pinfunction "2_2") (pintype "passive"))
      (node (ref "C20") (pin "2") (pinfunction "2_2") (pintype "passive"))
      (node (ref "C21") (pin "2") (pinfunction "2_2") (pintype "passive"))
      (node (ref "C22") (pin "2") (pinfunction "2_2") (pintype "passive"))
      (node (ref "C23") (pin "2") (pinfunction "2_2") (pintype "passive"))
      (node (ref "C24") (pin "2") (pinfunction "2_2") (pintype "passive"))
      (node (ref "C25") (pin "2") (pinfunction "2_2") (pintype "passive"))
      (node (ref "C26") (pin "2") (pinfunction "2_2") (pintype "passive"))
      (node (ref "C27") (pin "2") (pinfunction "2_2") (pintype "passive"))
      (node (ref "C28") (pin "2") (pinfunction "2_2") (pintype "passive"))
      (node (ref "C29") (pin "2") (pinfunction "2_2") (pintype "passive"))
      (node (ref "C3") (pin "2") (pinfunction "2_2") (pintype "passive"))
      (node (ref "C30") (pin "2") (pinfunction "2_2") (pintype "passive"))
      (node (ref "C31") (pin "2") (pinfunction "2_2") (pintype "passive"))
      (node (ref "C32") (pin "2") (pinfunction "2_2") (pintype "passive"))
      (node (ref "C33") (pin "2") (pinfunction "2_2") (pintype "passive"))
      (node (ref "C34") (pin "2") (pinfunction "2_2") (pintype "passive"))
      (node (ref "C35") (pin "2") (pinfunction "2_2") (pintype "passive"))
      (node (ref "C36") (pin "2") (pinfunction "2_2") (pintype "passive"))
      (node (ref "C37") (pin "2") (pinfunction "2_2") (pintype "passive"))
      (node (ref "C38") (pin "2") (pinfunction "2_2") (pintype "passive"))
      (node (ref "C39") (pin "2") (pinfunction "2_2") (pintype "passive"))
      (node (ref "C4") (pin "2") (pinfunction "2_2") (pintype "passive"))
      (node (ref "C5") (pin "2") (pinfunction "2_2") (pintype "passive"))
      (node (ref "C6") (pin "2") (pinfunction "2_2") (pintype "passive"))
      (node (ref "C7") (pin "2") (pinfunction "2_2") (pintype "passive"))
      (node (ref "C8") (pin "2") (pinfunction "2_2") (pintype "passive"))
      (node (ref "C9") (pin "2") (pinfunction "2_2") (pintype "passive"))
      (node (ref "CURR") (pin "B") (pinfunction "B_B") (pintype "passive"))
      (node (ref "CURRENT_SENSOR_SUPPLY") (pin "2") (pinfunction "2_2") (pintype "passive"))
      (node (ref "D1") (pin "C") (pinfunction "C_C") (pintype "passive"))
      (node (ref "D4") (pin "C") (pinfunction "C_C") (pintype "passive"))
      (node (ref "D7") (pin "C") (pinfunction "C_C") (pintype "passive"))
      (node (ref "D8") (pin "3") (pinfunction "3_3") (pintype "passive"))
      (node (ref "H1") (pin "B3,0") (pinfunction "MOUNT_B3,0") (pintype "passive"))
      (node (ref "H2") (pin "B3,0") (pinfunction "MOUNT_B3,0") (pintype "passive"))
      (node (ref "H3") (pin "B3,0") (pinfunction "MOUNT_B3,0") (pintype "passive"))
      (node (ref "H4") (pin "B3,0") (pinfunction "MOUNT_B3,0") (pintype "passive"))
      (node (ref "JP1") (pin "5") (pinfunction "5_5") (pintype "passive"))
      (node (ref "JP2") (pin "5") (pinfunction "5_5") (pintype "passive"))
      (node (ref "PWR") (pin "2") (pinfunction "2_2") (pintype "passive"))
      (node (ref "Q1") (pin "2") (pinfunction "S_2") (pintype "passive"))
      (node (ref "Q10") (pin "2") (pinfunction "S_2") (pintype "passive"))
      (node (ref "Q13") (pin "2") (pinfunction "S_2") (pintype "passive"))
      (node (ref "Q14") (pin "2") (pinfunction "S_2") (pintype "passive"))
      (node (ref "Q16") (pin "2") (pinfunction "S_2") (pintype "passive"))
      (node (ref "Q17") (pin "2") (pinfunction "S_2") (pintype "passive"))
      (node (ref "Q2") (pin "2") (pinfunction "S_2") (pintype "passive"))
      (node (ref "Q3") (pin "2") (pinfunction "S_2") (pintype "passive"))
      (node (ref "Q4") (pin "2") (pinfunction "S_2") (pintype "passive"))
      (node (ref "Q5") (pin "2") (pinfunction "S_2") (pintype "passive"))
      (node (ref "Q7") (pin "2") (pinfunction "S_2") (pintype "passive"))
      (node (ref "Q9") (pin "2") (pinfunction "S_2") (pintype "passive"))
      (node (ref "R16") (pin "1") (pinfunction "1_1") (pintype "passive"))
      (node (ref "R17") (pin "1") (pinfunction "1_1") (pintype "passive"))
      (node (ref "R18") (pin "1") (pinfunction "1_1") (pintype "passive"))
      (node (ref "R2") (pin "1") (pinfunction "1_1") (pintype "passive"))
      (node (ref "R30") (pin "1") (pinfunction "1_1") (pintype "passive"))
      (node (ref "R31") (pin "1") (pinfunction "1_1") (pintype "passive"))
      (node (ref "R32") (pin "1") (pinfunction "1_1") (pintype "passive"))
      (node (ref "R4") (pin "1") (pinfunction "1_1") (pintype "passive"))
      (node (ref "R40") (pin "1") (pinfunction "1_1") (pintype "passive"))
      (node (ref "R43") (pin "1") (pinfunction "1_1") (pintype "passive"))
      (node (ref "R7") (pin "1") (pinfunction "1_1") (pintype "passive"))
      (node (ref "R71") (pin "1") (pinfunction "1_1") (pintype "passive"))
      (node (ref "R72") (pin "1") (pinfunction "1_1") (pintype "passive"))
      (node (ref "R73") (pin "1") (pinfunction "1_1") (pintype "passive"))
      (node (ref "TSAL_EN") (pin "3") (pinfunction "3_3") (pintype "passive"))
      (node (ref "U$10") (pin "1") (pinfunction "GND_1") (pintype "bidirectional"))
      (node (ref "U$11") (pin "2") (pinfunction "VSS_2") (pintype "bidirectional"))
      (node (ref "U$12") (pin "2") (pinfunction "VSS_2") (pintype "passive"))
      (node (ref "U$16") (pin "2") (pinfunction "GND_2") (pintype "bidirectional"))
      (node (ref "U$17") (pin "2") (pinfunction "GND_2") (pintype "bidirectional"))
      (node (ref "U$18") (pin "2") (pinfunction "GND_2") (pintype "bidirectional"))
      (node (ref "U$20") (pin "2") (pinfunction "GND_2") (pintype "bidirectional"))
      (node (ref "U$21") (pin "A") (pinfunction "A_A") (pintype "passive"))
      (node (ref "U$22") (pin "2") (pinfunction "GND_2") (pintype "bidirectional"))
      (node (ref "U$23") (pin "2") (pinfunction "GND_2") (pintype "bidirectional"))
      (node (ref "U$24") (pin "2") (pinfunction "GND_2") (pintype "bidirectional"))
      (node (ref "U$25") (pin "A") (pinfunction "A_A") (pintype "passive"))
      (node (ref "U$26") (pin "A") (pinfunction "A_A") (pintype "passive"))
      (node (ref "U$29") (pin "A") (pinfunction "A_A") (pintype "passive"))
      (node (ref "U$32") (pin "A") (pinfunction "A_A") (pintype "passive"))
      (node (ref "U$33") (pin "A") (pinfunction "A_A") (pintype "passive"))
      (node (ref "U$34") (pin "A") (pinfunction "A_A") (pintype "passive"))
      (node (ref "U$36") (pin "A") (pinfunction "A_A") (pintype "passive"))
      (node (ref "U$37") (pin "A") (pinfunction "A_A") (pintype "passive"))
      (node (ref "U$38") (pin "A") (pinfunction "A_A") (pintype "passive"))
      (node (ref "U$39") (pin "A") (pinfunction "A_A") (pintype "passive"))
      (node (ref "U$4") (pin "2") (pinfunction "E_2") (pintype "passive"))
      (node (ref "U$5") (pin "2") (pinfunction "GND_2") (pintype "bidirectional"))
      (node (ref "U$7") (pin "2") (pinfunction "E_2") (pintype "passive"))
      (node (ref "U$8") (pin "2") (pinfunction "E_2") (pintype "passive"))
      (node (ref "U$9") (pin "1") (pinfunction "GND_1") (pintype "bidirectional"))
      (node (ref "U1") (pin "20") (pinfunction "PB2_20") (pintype "bidirectional"))
      (node (ref "U1") (pin "23") (pinfunction "VSS_1_23") (pintype "bidirectional"))
      (node (ref "U1") (pin "35") (pinfunction "VSS_2_35") (pintype "passive"))
      (node (ref "U1") (pin "44") (pinfunction "BOOT0_44") (pintype "bidirectional"))
      (node (ref "U1") (pin "47") (pinfunction "VSS_3_47") (pintype "passive"))
      (node (ref "U1") (pin "8") (pinfunction "VSSA_8") (pintype "passive"))
      (node (ref "U2") (pin "20") (pinfunction "PB2_20") (pintype "bidirectional"))
      (node (ref "U2") (pin "23") (pinfunction "VSS_1_23") (pintype "bidirectional"))
      (node (ref "U2") (pin "35") (pinfunction "VSS_2_35") (pintype "passive"))
      (node (ref "U2") (pin "44") (pinfunction "BOOT0_44") (pintype "bidirectional"))
      (node (ref "U2") (pin "47") (pinfunction "VSS_3_47") (pintype "passive"))
      (node (ref "U2") (pin "8") (pinfunction "VSSA_8") (pintype "passive"))
    )
    (net (code "44") (name "HALL_FL") (class "Default")
      (node (ref "HALL_SENSE") (pin "1") (pinfunction "1_1") (pintype "passive"))
      (node (ref "R57") (pin "1") (pinfunction "1_1") (pintype "passive"))
    )
    (net (code "45") (name "HALL_FL_F") (class "Default")
      (node (ref "C33") (pin "1") (pinfunction "1_1") (pintype "passive"))
      (node (ref "R58") (pin "2") (pinfunction "2_2") (pintype "passive"))
      (node (ref "U2") (pin "11") (pinfunction "PA1_11") (pintype "bidirectional"))
    )
    (net (code "46") (name "HALL_FR") (class "Default")
      (node (ref "HALL_SENSE") (pin "3") (pinfunction "3_3") (pintype "passive"))
      (node (ref "R59") (pin "1") (pinfunction "1_1") (pintype "passive"))
    )
    (net (code "47") (name "HALL_FR_F") (class "Default")
      (node (ref "C34") (pin "1") (pinfunction "1_1") (pintype "passive"))
      (node (ref "R60") (pin "2") (pinfunction "2_2") (pintype "passive"))
      (node (ref "U2") (pin "10") (pinfunction "PA0-WKUP_10") (pintype "bidirectional"))
    )
    (net (code "48") (name "HALL_RL") (class "Default")
      (node (ref "HALL_SENSE") (pin "2") (pinfunction "2_2") (pintype "passive"))
      (node (ref "R61") (pin "1") (pinfunction "1_1") (pintype "passive"))
    )
    (net (code "49") (name "HALL_RL_F") (class "Default")
      (node (ref "C35") (pin "1") (pinfunction "1_1") (pintype "passive"))
      (node (ref "R62") (pin "2") (pinfunction "2_2") (pintype "passive"))
      (node (ref "U2") (pin "12") (pinfunction "PA2_12") (pintype "bidirectional"))
    )
    (net (code "50") (name "HALL_RR") (class "Default")
      (node (ref "HALL_SENSE") (pin "4") (pinfunction "4_4") (pintype "passive"))
      (node (ref "R63") (pin "1") (pinfunction "1_1") (pintype "passive"))
    )
    (net (code "51") (name "HALL_RR_F") (class "Default")
      (node (ref "C36") (pin "1") (pinfunction "1_1") (pintype "passive"))
      (node (ref "R64") (pin "2") (pinfunction "2_2") (pintype "passive"))
      (node (ref "U2") (pin "13") (pinfunction "PA3_13") (pintype "bidirectional"))
    )
    (net (code "52") (name "HV_CONNECTED_3_3") (class "Default")
      (node (ref "Q10") (pin "3") (pinfunction "D_3") (pintype "passive"))
      (node (ref "R23") (pin "1") (pinfunction "1_1") (pintype "passive"))
      (node (ref "U1") (pin "21") (pinfunction "PB10_21") (pintype "bidirectional"))
    )
    (net (code "53") (name "Net-(C17-Pad1)") (class "Default")
      (node (ref "C17") (pin "1") (pinfunction "1_1") (pintype "passive"))
      (node (ref "R19") (pin "1") (pinfunction "1_1") (pintype "passive"))
    )
    (net (code "54") (name "Net-(C18-Pad1)") (class "Default")
      (node (ref "C18") (pin "1") (pinfunction "1_1") (pintype "passive"))
      (node (ref "R20") (pin "1") (pinfunction "1_1") (pintype "passive"))
    )
    (net (code "55") (name "Net-(D1-PadA)") (class "Default")
      (node (ref "D1") (pin "A") (pinfunction "A_A") (pintype "passive"))
      (node (ref "R21") (pin "2") (pinfunction "2_2") (pintype "passive"))
    )
    (net (code "56") (name "Net-(D4-PadA)") (class "Default")
      (node (ref "D4") (pin "A") (pinfunction "A_A") (pintype "passive"))
      (node (ref "R22") (pin "2") (pinfunction "2_2") (pintype "passive"))
    )
    (net (code "57") (name "Net-(D7-PadA)") (class "Default")
      (node (ref "D7") (pin "A") (pinfunction "A_A") (pintype "passive"))
      (node (ref "R15") (pin "2") (pinfunction "2_2") (pintype "passive"))
    )
    (net (code "58") (name "Net-(D10-PadA)") (class "Default")
      (node (ref "D10") (pin "A") (pinfunction "A_A") (pintype "passive"))
      (node (ref "R27") (pin "2") (pinfunction "2_2") (pintype "passive"))
    )
    (net (code "59") (name "Net-(D11-PadC)") (class "Default")
      (node (ref "D11") (pin "C") (pinfunction "C_C") (pintype "passive"))
      (node (ref "R2") (pin "2") (pinfunction "2_2") (pintype "passive"))
    )
    (net (code "60") (name "Net-(D12-PadC)") (class "Default")
      (node (ref "D12") (pin "C") (pinfunction "C_C") (pintype "passive"))
      (node (ref "R4") (pin "2") (pinfunction "2_2") (pintype "passive"))
    )
    (net (code "61") (name "Net-(D13-PadA)") (class "Default")
      (node (ref "D13") (pin "A") (pinfunction "A_A") (pintype "passive"))
      (node (ref "R29") (pin "2") (pinfunction "2_2") (pintype "passive"))
    )
    (net (code "62") (name "Net-(L4-1)") (class "Default")
      (node (ref "FUSE") (pin "P$2") (pinfunction "2_P$2") (pintype "passive"))
      (node (ref "FUSE") (pin "P$3") (pinfunction "2_P$3") (pintype "passive"))
      (node (ref "L4") (pin "P$1") (pinfunction "1_P$1") (pintype "passive"))
    )
    (net (code "63") (name "Net-(Q3-D)") (class "Default")
      (node (ref "D9") (pin "A") (pinfunction "A_A") (pintype "passive"))
      (node (ref "Q3") (pin "3") (pinfunction "D_3") (pintype "passive"))
      (node (ref "U$14") (pin "$P12") (pinfunction "$P12_$P12") (pintype "bidirectional"))
    )
    (net (code "64") (name "Net-(Q5-D)") (class "Default")
      (node (ref "D2") (pin "A") (pinfunction "A_A") (pintype "passive"))
      (node (ref "Q5") (pin "3") (pinfunction "D_3") (pintype "passive"))
      (node (ref "U$13") (pin "$P12") (pinfunction "$P12_$P12") (pintype "bidirectional"))
    )
    (net (code "65") (name "Net-(Q6-D)") (class "Default")
      (node (ref "Q6") (pin "3") (pinfunction "D_3") (pintype "passive"))
      (node (ref "U$13") (pin "$P3") (pinfunction "$P3_$P3") (pintype "passive"))
    )
    (net (code "66") (name "Net-(Q11-D)") (class "Default")
      (node (ref "Q11") (pin "3") (pinfunction "D_3") (pintype "passive"))
      (node (ref "U$14") (pin "$P3") (pinfunction "$P3_$P3") (pintype "passive"))
    )
    (net (code "67") (name "Net-(Q12-S)") (class "Default")
      (node (ref "Q12") (pin "2") (pinfunction "S_2") (pintype "passive"))
      (node (ref "Q13") (pin "3") (pinfunction "D_3") (pintype "passive"))
    )
    (net (code "68") (name "Net-(Q15-D)") (class "Default")
      (node (ref "Q15") (pin "3") (pinfunction "D_3") (pintype "passive"))
      (node (ref "U$15") (pin "$P3") (pinfunction "$P3_$P3") (pintype "passive"))
    )
    (net (code "69") (name "Net-(Q16-D)") (class "Default")
      (node (ref "D15") (pin "A") (pinfunction "A_A") (pintype "passive"))
      (node (ref "Q16") (pin "3") (pinfunction "D_3") (pintype "passive"))
      (node (ref "U$15") (pin "$P12") (pinfunction "$P12_$P12") (pintype "bidirectional"))
    )
    (net (code "70") (name "Net-(Q18-D)") (class "Default")
      (node (ref "Q18") (pin "3") (pinfunction "D_3") (pintype "passive"))
      (node (ref "Q20") (pin "2") (pinfunction "S_2") (pintype "passive"))
    )
    (net (code "71") (name "Net-(Q18-S)") (class "Default")
      (node (ref "Q18") (pin "2") (pinfunction "S_2") (pintype "passive"))
      (node (ref "Q21") (pin "3") (pinfunction "D_3") (pintype "passive"))
    )
    (net (code "72") (name "Net-(R33-Pad2)") (class "Default")
      (node (ref "R33") (pin "2") (pinfunction "2_2") (pintype "passive"))
      (node (ref "R34") (pin "1") (pinfunction "1_1") (pintype "passive"))
      (node (ref "U$25") (pin "C") (pinfunction "C_C") (pintype "passive"))
    )
    (net (code "73") (name "Net-(R35-Pad1)") (class "Default")
      (node (ref "R35") (pin "1") (pinfunction "1_1") (pintype "passive"))
      (node (ref "R53") (pin "2") (pinfunction "2_2") (pintype "passive"))
      (node (ref "R54") (pin "1") (pinfunction "1_1") (pintype "passive"))
      (node (ref "U$34") (pin "C") (pinfunction "C_C") (pintype "passive"))
    )
    (net (code "74") (name "Net-(R37-Pad2)") (class "Default")
      (node (ref "R37") (pin "2") (pinfunction "2_2") (pintype "passive"))
      (node (ref "R38") (pin "1") (pinfunction "1_1") (pintype "passive"))
      (node (ref "U$26") (pin "C") (pinfunction "C_C") (pintype "passive"))
    )
    (net (code "75") (name "Net-(R41-Pad2)") (class "Default")
      (node (ref "R41") (pin "2") (pinfunction "2_2") (pintype "passive"))
      (node (ref "R42") (pin "1") (pinfunction "1_1") (pintype "passive"))
      (node (ref "U$29") (pin "C") (pinfunction "C_C") (pintype "passive"))
    )
    (net (code "76") (name "Net-(R49-Pad2)") (class "Default")
      (node (ref "R49") (pin "2") (pinfunction "2_2") (pintype "passive"))
      (node (ref "R50") (pin "1") (pinfunction "1_1") (pintype "passive"))
      (node (ref "U$32") (pin "C") (pinfunction "C_C") (pintype "passive"))
    )
    (net (code "77") (name "Net-(R51-Pad2)") (class "Default")
      (node (ref "R51") (pin "2") (pinfunction "2_2") (pintype "passive"))
      (node (ref "R52") (pin "1") (pinfunction "1_1") (pintype "passive"))
      (node (ref "U$33") (pin "C") (pinfunction "C_C") (pintype "passive"))
    )
    (net (code "78") (name "Net-(R55-Pad2)") (class "Default")
      (node (ref "R55") (pin "2") (pinfunction "2_2") (pintype "passive"))
      (node (ref "R56") (pin "1") (pinfunction "1_1") (pintype "passive"))
      (node (ref "U$21") (pin "C") (pinfunction "C_C") (pintype "passive"))
    )
    (net (code "79") (name "Net-(R57-Pad2)") (class "Default")
      (node (ref "R57") (pin "2") (pinfunction "2_2") (pintype "passive"))
      (node (ref "R58") (pin "1") (pinfunction "1_1") (pintype "passive"))
      (node (ref "R65") (pin "1") (pinfunction "1_1") (pintype "passive"))
      (node (ref "U$36") (pin "C") (pinfunction "C_C") (pintype "passive"))
    )
    (net (code "80") (name "Net-(R59-Pad2)") (class "Default")
      (node (ref "R59") (pin "2") (pinfunction "2_2") (pintype "passive"))
      (node (ref "R60") (pin "1") (pinfunction "1_1") (pintype "passive"))
      (node (ref "R66") (pin "1") (pinfunction "1_1") (pintype "passive"))
      (node (ref "U$37") (pin "C") (pinfunction "C_C") (pintype "passive"))
    )
    (net (code "81") (name "Net-(R61-Pad2)") (class "Default")
      (node (ref "R61") (pin "2") (pinfunction "2_2") (pintype "passive"))
      (node (ref "R62") (pin "1") (pinfunction "1_1") (pintype "passive"))
      (node (ref "R67") (pin "1") (pinfunction "1_1") (pintype "passive"))
      (node (ref "U$38") (pin "C") (pinfunction "C_C") (pintype "passive"))
    )
    (net (code "82") (name "Net-(R63-Pad2)") (class "Default")
      (node (ref "R63") (pin "2") (pinfunction "2_2") (pintype "passive"))
      (node (ref "R64") (pin "1") (pinfunction "1_1") (pintype "passive"))
      (node (ref "R68") (pin "1") (pinfunction "1_1") (pintype "passive"))
      (node (ref "U$39") (pin "C") (pinfunction "C_C") (pintype "passive"))
    )
    (net (code "83") (name "Net-(U$4-B)") (class "Default")
      (node (ref "R9") (pin "2") (pinfunction "2_2") (pintype "passive"))
      (node (ref "U$4") (pin "1") (pinfunction "B_1") (pintype "passive"))
    )
    (net (code "84") (name "Net-(U$5-OUT)") (class "Default")
      (node (ref "R1") (pin "2") (pinfunction "2_2") (pintype "passive"))
      (node (ref "U$5") (pin "1") (pinfunction "OUT_1") (pintype "output"))
    )
    (net (code "85") (name "Net-(U$7-B)") (class "Default")
      (node (ref "R6") (pin "2") (pinfunction "2_2") (pintype "passive"))
      (node (ref "U$7") (pin "1") (pinfunction "B_1") (pintype "passive"))
    )
    (net (code "86") (name "Net-(U$8-B)") (class "Default")
      (node (ref "R3") (pin "2") (pinfunction "2_2") (pintype "passive"))
      (node (ref "U$8") (pin "1") (pinfunction "B_1") (pintype "passive"))
    )
    (net (code "87") (name "Net-(U$12-B)") (class "Default")
      (node (ref "R7") (pin "2") (pinfunction "2_2") (pintype "passive"))
      (node (ref "U$12") (pin "5") (pinfunction "B_5") (pintype "passive"))
      (node (ref "U$18") (pin "1") (pinfunction "+IN_1") (pintype "input"))
    )
    (net (code "88") (name "Net-(U$13-Pad$P8)") (class "Default")
      (node (ref "U$13") (pin "$P8") (pinfunction "$P8_$P8") (pintype "passive"))
      (node (ref "U$14") (pin "$P9") (pinfunction "$P9_$P9") (pintype "passive"))
    )
    (net (code "89") (name "Net-(U$14-Pad$P8)") (class "Default")
      (node (ref "U$14") (pin "$P8") (pinfunction "$P8_$P8") (pintype "passive"))
      (node (ref "U$15") (pin "$P9") (pinfunction "$P9_$P9") (pintype "passive"))
    )
    (net (code "90") (name "Net-(U$20-OUT)") (class "Default")
      (node (ref "R36") (pin "2") (pinfunction "2_2") (pintype "passive"))
      (node (ref "U$20") (pin "1") (pinfunction "OUT_1") (pintype "output"))
    )
    (net (code "91") (name "Net-(U$22-+IN)") (class "Default")
      (node (ref "C29") (pin "1") (pinfunction "1_1") (pintype "passive"))
      (node (ref "R50") (pin "2") (pinfunction "2_2") (pintype "passive"))
      (node (ref "U$22") (pin "1") (pinfunction "+IN_1") (pintype "input"))
    )
    (net (code "92") (name "Net-(U$23-+IN)") (class "Default")
      (node (ref "C30") (pin "1") (pinfunction "1_1") (pintype "passive"))
      (node (ref "R52") (pin "2") (pinfunction "2_2") (pintype "passive"))
      (node (ref "U$23") (pin "1") (pinfunction "+IN_1") (pintype "input"))
    )
    (net (code "93") (name "Net-(U$24-+IN)") (class "Default")
      (node (ref "C31") (pin "1") (pinfunction "1_1") (pintype "passive"))
      (node (ref "R54") (pin "2") (pinfunction "2_2") (pintype "passive"))
      (node (ref "U$24") (pin "1") (pinfunction "+IN_1") (pintype "input"))
    )
    (net (code "94") (name "OC_TH") (class "Default")
      (node (ref "R11") (pin "1") (pinfunction "1_1") (pintype "passive"))
      (node (ref "R43") (pin "2") (pinfunction "2_2") (pintype "passive"))
      (node (ref "U$17") (pin "4") (pinfunction "-IN_4") (pintype "input"))
    )
    (net (code "95") (name "PA11") (class "Default")
      (node (ref "U2") (pin "32") (pinfunction "PA11_32") (pintype "power_in"))
    )
    (net (code "96") (name "PRECHARGE_COMPLETE") (class "Default")
      (node (ref "R55") (pin "1") (pinfunction "1_1") (pintype "passive"))
      (node (ref "THROTTLE") (pin "3") (pinfunction "3_3") (pintype "passive"))
    )
    (net (code "97") (name "PRECHARGE_COMPLETE_3_3") (class "Default")
      (node (ref "Q7") (pin "3") (pinfunction "D_3") (pintype "passive"))
      (node (ref "R74") (pin "1") (pinfunction "1_1") (pintype "passive"))
      (node (ref "U1") (pin "42") (pinfunction "PB6_42") (pintype "bidirectional"))
    )
    (net (code "98") (name "PRECHARGE_COMP_F") (class "Default")
      (node (ref "C32") (pin "1") (pinfunction "1_1") (pintype "passive"))
      (node (ref "Q7") (pin "1") (pinfunction "G_1") (pintype "passive"))
      (node (ref "R56") (pin "2") (pinfunction "2_2") (pintype "passive"))
    )
    (net (code "99") (name "PWR") (class "Default")
      (node (ref "FUSE") (pin "P$1") (pinfunction "1_P$1") (pintype "passive"))
      (node (ref "FUSE") (pin "P$4") (pinfunction "1_P$4") (pintype "passive"))
      (node (ref "PWR") (pin "1") (pinfunction "1_1") (pintype "passive"))
    )
    (net (code "100") (name "RTDS-") (class "Default")
      (node (ref "DRIVERS") (pin "3") (pinfunction "3_3") (pintype "passive"))
      (node (ref "Q4") (pin "3") (pinfunction "D_3") (pintype "passive"))
    )
    (net (code "101") (name "RTDS_EN") (class "Default")
      (node (ref "Q4") (pin "1") (pinfunction "G_1") (pintype "passive"))
      (node (ref "U1") (pin "39") (pinfunction "PB3_39") (pintype "bidirectional"))
    )
    (net (code "102") (name "RTD_EN") (class "Default")
      (node (ref "Q21") (pin "1") (pinfunction "G_1") (pintype "passive"))
      (node (ref "R32") (pin "2") (pinfunction "2_2") (pintype "passive"))
      (node (ref "U1") (pin "45") (pinfunction "PB8_45") (pintype "bidirectional"))
    )
    (net (code "103") (name "SCL_TC") (class "Default")
      (node (ref "R48") (pin "2") (pinfunction "2_2") (pintype "passive"))
      (node (ref "U$12") (pin "3") (pinfunction "SCL_3") (pintype "passive"))
      (node (ref "U2") (pin "42") (pinfunction "PB6_42") (pintype "bidirectional"))
    )
    (net (code "104") (name "SC_TH") (class "Default")
      (node (ref "R39") (pin "1") (pinfunction "1_1") (pintype "passive"))
      (node (ref "R40") (pin "2") (pinfunction "2_2") (pintype "passive"))
      (node (ref "U$16") (pin "3") (pinfunction "+IN_3") (pintype "input"))
    )
    (net (code "105") (name "SDA_TC") (class "Default")
      (node (ref "R47") (pin "2") (pinfunction "2_2") (pintype "passive"))
      (node (ref "U$12") (pin "4") (pinfunction "SDA_4") (pintype "passive"))
      (node (ref "U2") (pin "43") (pinfunction "PB7_43") (pintype "bidirectional"))
    )
    (net (code "106") (name "SPI1_MISO") (class "Default")
      (node (ref "U1") (pin "16") (pinfunction "PA6_16") (pintype "bidirectional"))
      (node (ref "U2") (pin "17") (pinfunction "PA7_17") (pintype "bidirectional"))
    )
    (net (code "107") (name "SPI1_MOSI") (class "Default")
      (node (ref "U1") (pin "17") (pinfunction "PA7_17") (pintype "bidirectional"))
      (node (ref "U2") (pin "16") (pinfunction "PA6_16") (pintype "bidirectional"))
    )
    (net (code "108") (name "SPI1_NSS") (class "Default")
      (node (ref "U1") (pin "14") (pinfunction "PA4_14") (pintype "bidirectional"))
      (node (ref "U2") (pin "14") (pinfunction "PA4_14") (pintype "bidirectional"))
    )
    (net (code "109") (name "SPI1_SCK") (class "Default")
      (node (ref "U1") (pin "15") (pinfunction "PA5_15") (pintype "bidirectional"))
      (node (ref "U2") (pin "15") (pinfunction "PA5_15") (pintype "bidirectional"))
    )
    (net (code "110") (name "SWCLK") (class "Default")
      (node (ref "JP1") (pin "4") (pinfunction "4_4") (pintype "passive"))
      (node (ref "U1") (pin "37") (pinfunction "PA14_37") (pintype "bidirectional"))
    )
    (net (code "111") (name "SWCLK_TC") (class "Default")
      (node (ref "JP2") (pin "4") (pinfunction "4_4") (pintype "passive"))
      (node (ref "U2") (pin "37") (pinfunction "PA14_37") (pintype "bidirectional"))
    )
    (net (code "112") (name "SWDIO") (class "Default")
      (node (ref "JP1") (pin "3") (pinfunction "3_3") (pintype "passive"))
      (node (ref "U1") (pin "34") (pinfunction "PA13_34") (pintype "bidirectional"))
    )
    (net (code "113") (name "SWDIO_TC") (class "Default")
      (node (ref "JP2") (pin "3") (pinfunction "3_3") (pintype "passive"))
      (node (ref "U2") (pin "34") (pinfunction "PA13_34") (pintype "bidirectional"))
    )
    (net (code "114") (name "THROTTLE_A") (class "Default")
      (node (ref "R49") (pin "1") (pinfunction "1_1") (pintype "passive"))
      (node (ref "THROTTLE") (pin "1") (pinfunction "1_1") (pintype "passive"))
    )
    (net (code "115") (name "THROTTLE_A_F") (class "Default")
      (node (ref "R69") (pin "2") (pinfunction "2_2") (pintype "passive"))
      (node (ref "U$12") (pin "6") (pinfunction "W_6") (pintype "passive"))
      (node (ref "U$22") (pin "3") (pinfunction "-IN_3") (pintype "input"))
      (node (ref "U$22") (pin "4") (pinfunction "OUT_4") (pintype "output"))
    )
    (net (code "116") (name "THROTTLE_A_F_3_3") (class "Default")
      (node (ref "R69") (pin "1") (pinfunction "1_1") (pintype "passive"))
      (node (ref "R73") (pin "2") (pinfunction "2_2") (pintype "passive"))
      (node (ref "U1") (pin "18") (pinfunction "PB0_18") (pintype "bidirectional"))
    )
    (net (code "117") (name "THROTTLE_B") (class "Default")
      (node (ref "R51") (pin "1") (pinfunction "1_1") (pintype "passive"))
      (node (ref "THROTTLE") (pin "2") (pinfunction "2_2") (pintype "passive"))
    )
    (net (code "118") (name "THROTTLE_B_F") (class "Default")
      (node (ref "R46") (pin "2") (pinfunction "2_2") (pintype "passive"))
      (node (ref "U$23") (pin "3") (pinfunction "-IN_3") (pintype "input"))
      (node (ref "U$23") (pin "4") (pinfunction "OUT_4") (pintype "output"))
    )
    (net (code "119") (name "THROTTLE_B_F_3_3") (class "Default")
      (node (ref "R46") (pin "1") (pinfunction "1_1") (pintype "passive"))
      (node (ref "R72") (pin "2") (pinfunction "2_2") (pintype "passive"))
      (node (ref "U1") (pin "19") (pinfunction "PB1_19") (pintype "bidirectional"))
    )
    (net (code "120") (name "THROTTLE_OUT") (class "Default")
      (node (ref "THROTTLE") (pin "4") (pinfunction "4_4") (pintype "passive"))
      (node (ref "U$18") (pin "3") (pinfunction "-IN_3") (pintype "input"))
      (node (ref "U$18") (pin "4") (pinfunction "OUT_4") (pintype "output"))
    )
    (net (code "121") (name "TSAL_EN") (class "Default")
      (node (ref "Q10") (pin "1") (pinfunction "G_1") (pintype "passive"))
      (node (ref "TSAL_EN") (pin "2") (pinfunction "2_2") (pintype "passive"))
    )
    (net (code "122") (name "TSAL_HV-") (class "Default")
      (node (ref "DRIVERS") (pin "4") (pinfunction "4_4") (pintype "passive"))
      (node (ref "U$8") (pin "3") (pinfunction "C_3") (pintype "passive"))
    )
    (net (code "123") (name "TSAL_HV_EN") (class "Default")
      (node (ref "R3") (pin "1") (pinfunction "1_1") (pintype "passive"))
      (node (ref "U1") (pin "22") (pinfunction "PB11_22") (pintype "bidirectional"))
    )
    (net (code "124") (name "TSAL_LV-") (class "Default")
      (node (ref "DRIVERS") (pin "2") (pinfunction "2_2") (pintype "passive"))
      (node (ref "U$7") (pin "3") (pinfunction "C_3") (pintype "passive"))
    )
    (net (code "125") (name "TSAL_LV_EN") (class "Default")
      (node (ref "R6") (pin "1") (pinfunction "1_1") (pintype "passive"))
      (node (ref "U1") (pin "25") (pinfunction "PB12_25") (pintype "bidirectional"))
    )
    (net (code "126") (name "unconnected-(U$13-Pad$P10)") (class "Default")
      (node (ref "U$13") (pin "$P10") (pinfunction "$P10_$P10") (pintype "passive"))
    )
    (net (code "127") (name "unconnected-(U$14-Pad$P10)") (class "Default")
      (node (ref "U$14") (pin "$P10") (pinfunction "$P10_$P10") (pintype "passive"))
    )
    (net (code "128") (name "unconnected-(U$15-Pad$P10)") (class "Default")
      (node (ref "U$15") (pin "$P10") (pinfunction "$P10_$P10") (pintype "passive"))
    )
    (net (code "129") (name "unconnected-(U1-PA1-Pad11)") (class "Default")
      (node (ref "U1") (pin "11") (pinfunction "PA1_11") (pintype "bidirectional"))
    )
    (net (code "130") (name "unconnected-(U1-PA8-Pad29)") (class "Default")
      (node (ref "U1") (pin "29") (pinfunction "PA8_29") (pintype "bidirectional"))
    )
    (net (code "131") (name "unconnected-(U1-PA9-Pad30)") (class "Default")
      (node (ref "U1") (pin "30") (pinfunction "PA9_30") (pintype "bidirectional"))
    )
    (net (code "132") (name "unconnected-(U1-PA15-Pad38)") (class "Default")
      (node (ref "U1") (pin "38") (pinfunction "PA15_38") (pintype "bidirectional"))
    )
    (net (code "133") (name "unconnected-(U1-PB7-Pad43)") (class "Default")
      (node (ref "U1") (pin "43") (pinfunction "PB7_43") (pintype "bidirectional"))
    )
    (net (code "134") (name "unconnected-(U1-PB9-Pad46)") (class "Default")
      (node (ref "U1") (pin "46") (pinfunction "PB9_46") (pintype "bidirectional"))
    )
    (net (code "135") (name "unconnected-(U1-PB15-Pad28)") (class "Default")
      (node (ref "U1") (pin "28") (pinfunction "PB15_28") (pintype "bidirectional"))
    )
    (net (code "136") (name "unconnected-(U1-PC14-OSC32_IN-Pad3)") (class "Default")
      (node (ref "U1") (pin "3") (pinfunction "PC14-OSC32_IN_3") (pintype "bidirectional"))
    )
    (net (code "137") (name "unconnected-(U1-PC15-OSC32_OUT-Pad4)") (class "Default")
      (node (ref "U1") (pin "4") (pinfunction "PC15-OSC32_OUT_4") (pintype "bidirectional"))
    )
    (net (code "138") (name "unconnected-(U1-PD0-OSC_IN-Pad5)") (class "Default")
      (node (ref "U1") (pin "5") (pinfunction "PD0-OSC_IN_5") (pintype "bidirectional"))
    )
    (net (code "139") (name "unconnected-(U1-PD1-OSC_OUT-Pad6)") (class "Default")
      (node (ref "U1") (pin "6") (pinfunction "PD1-OSC_OUT_6") (pintype "bidirectional"))
    )
    (net (code "140") (name "unconnected-(U1-VBAT-Pad1)") (class "Default")
      (node (ref "U1") (pin "1") (pinfunction "VBAT_1") (pintype "input"))
    )
    (net (code "141") (name "unconnected-(U2-PA8-Pad29)") (class "Default")
      (node (ref "U2") (pin "29") (pinfunction "PA8_29") (pintype "bidirectional"))
    )
    (net (code "142") (name "unconnected-(U2-PA9-Pad30)") (class "Default")
      (node (ref "U2") (pin "30") (pinfunction "PA9_30") (pintype "bidirectional"))
    )
    (net (code "143") (name "unconnected-(U2-PA10-Pad31)") (class "Default")
      (node (ref "U2") (pin "31") (pinfunction "PA10_31") (pintype "bidirectional"))
    )
    (net (code "144") (name "unconnected-(U2-PA12-Pad33)") (class "Default")
      (node (ref "U2") (pin "33") (pinfunction "PA12_33") (pintype "bidirectional"))
    )
    (net (code "145") (name "unconnected-(U2-PA15-Pad38)") (class "Default")
      (node (ref "U2") (pin "38") (pinfunction "PA15_38") (pintype "bidirectional"))
    )
    (net (code "146") (name "unconnected-(U2-PB0-Pad18)") (class "Default")
      (node (ref "U2") (pin "18") (pinfunction "PB0_18") (pintype "bidirectional"))
    )
    (net (code "147") (name "unconnected-(U2-PB1-Pad19)") (class "Default")
      (node (ref "U2") (pin "19") (pinfunction "PB1_19") (pintype "bidirectional"))
    )
    (net (code "148") (name "unconnected-(U2-PB3-Pad39)") (class "Default")
      (node (ref "U2") (pin "39") (pinfunction "PB3_39") (pintype "bidirectional"))
    )
    (net (code "149") (name "unconnected-(U2-PB4-Pad40)") (class "Default")
      (node (ref "U2") (pin "40") (pinfunction "PB4_40") (pintype "bidirectional"))
    )
    (net (code "150") (name "unconnected-(U2-PB5-Pad41)") (class "Default")
      (node (ref "U2") (pin "41") (pinfunction "PB5_41") (pintype "bidirectional"))
    )
    (net (code "151") (name "unconnected-(U2-PB8-Pad45)") (class "Default")
      (node (ref "U2") (pin "45") (pinfunction "PB8_45") (pintype "bidirectional"))
    )
    (net (code "152") (name "unconnected-(U2-PB9-Pad46)") (class "Default")
      (node (ref "U2") (pin "46") (pinfunction "PB9_46") (pintype "bidirectional"))
    )
    (net (code "153") (name "unconnected-(U2-PB10-Pad21)") (class "Default")
      (node (ref "U2") (pin "21") (pinfunction "PB10_21") (pintype "bidirectional"))
    )
    (net (code "154") (name "unconnected-(U2-PB11-Pad22)") (class "Default")
      (node (ref "U2") (pin "22") (pinfunction "PB11_22") (pintype "bidirectional"))
    )
    (net (code "155") (name "unconnected-(U2-PB12-Pad25)") (class "Default")
      (node (ref "U2") (pin "25") (pinfunction "PB12_25") (pintype "bidirectional"))
    )
    (net (code "156") (name "unconnected-(U2-PB13-Pad26)") (class "Default")
      (node (ref "U2") (pin "26") (pinfunction "PB13_26") (pintype "bidirectional"))
    )
    (net (code "157") (name "unconnected-(U2-PB14-Pad27)") (class "Default")
      (node (ref "U2") (pin "27") (pinfunction "PB14_27") (pintype "bidirectional"))
    )
    (net (code "158") (name "unconnected-(U2-PB15-Pad28)") (class "Default")
      (node (ref "U2") (pin "28") (pinfunction "PB15_28") (pintype "bidirectional"))
    )
    (net (code "159") (name "unconnected-(U2-PC14-OSC32_IN-Pad3)") (class "Default")
      (node (ref "U2") (pin "3") (pinfunction "PC14-OSC32_IN_3") (pintype "bidirectional"))
    )
    (net (code "160") (name "unconnected-(U2-PC15-OSC32_OUT-Pad4)") (class "Default")
      (node (ref "U2") (pin "4") (pinfunction "PC15-OSC32_OUT_4") (pintype "bidirectional"))
    )
    (net (code "161") (name "unconnected-(U2-PD0-OSC_IN-Pad5)") (class "Default")
      (node (ref "U2") (pin "5") (pinfunction "PD0-OSC_IN_5") (pintype "bidirectional"))
    )
    (net (code "162") (name "unconnected-(U2-PD1-OSC_OUT-Pad6)") (class "Default")
      (node (ref "U2") (pin "6") (pinfunction "PD1-OSC_OUT_6") (pintype "bidirectional"))
    )
    (net (code "163") (name "unconnected-(U2-VBAT-Pad1)") (class "Default")
      (node (ref "U2") (pin "1") (pinfunction "VBAT_1") (pintype "input"))
    )
    (net (code "164") (name "~{RST_TC}") (class "Default")
      (node (ref "JP2") (pin "2") (pinfunction "2_2") (pintype "passive"))
      (node (ref "R28") (pin "2") (pinfunction "2_2") (pintype "passive"))
      (node (ref "U2") (pin "7") (pinfunction "NRST_7") (pintype "bidirectional"))
    )
    (net (code "165") (name "~{RST}") (class "Default")
      (node (ref "JP1") (pin "2") (pinfunction "2_2") (pintype "passive"))
      (node (ref "R26") (pin "2") (pinfunction "2_2") (pintype "passive"))
      (node (ref "U1") (pin "7") (pinfunction "NRST_7") (pintype "bidirectional"))
    )
  )
)
